# Super_Clokk_199774_2015_03_30.net
KiCad netlist of a schematic drawn in EAGLE
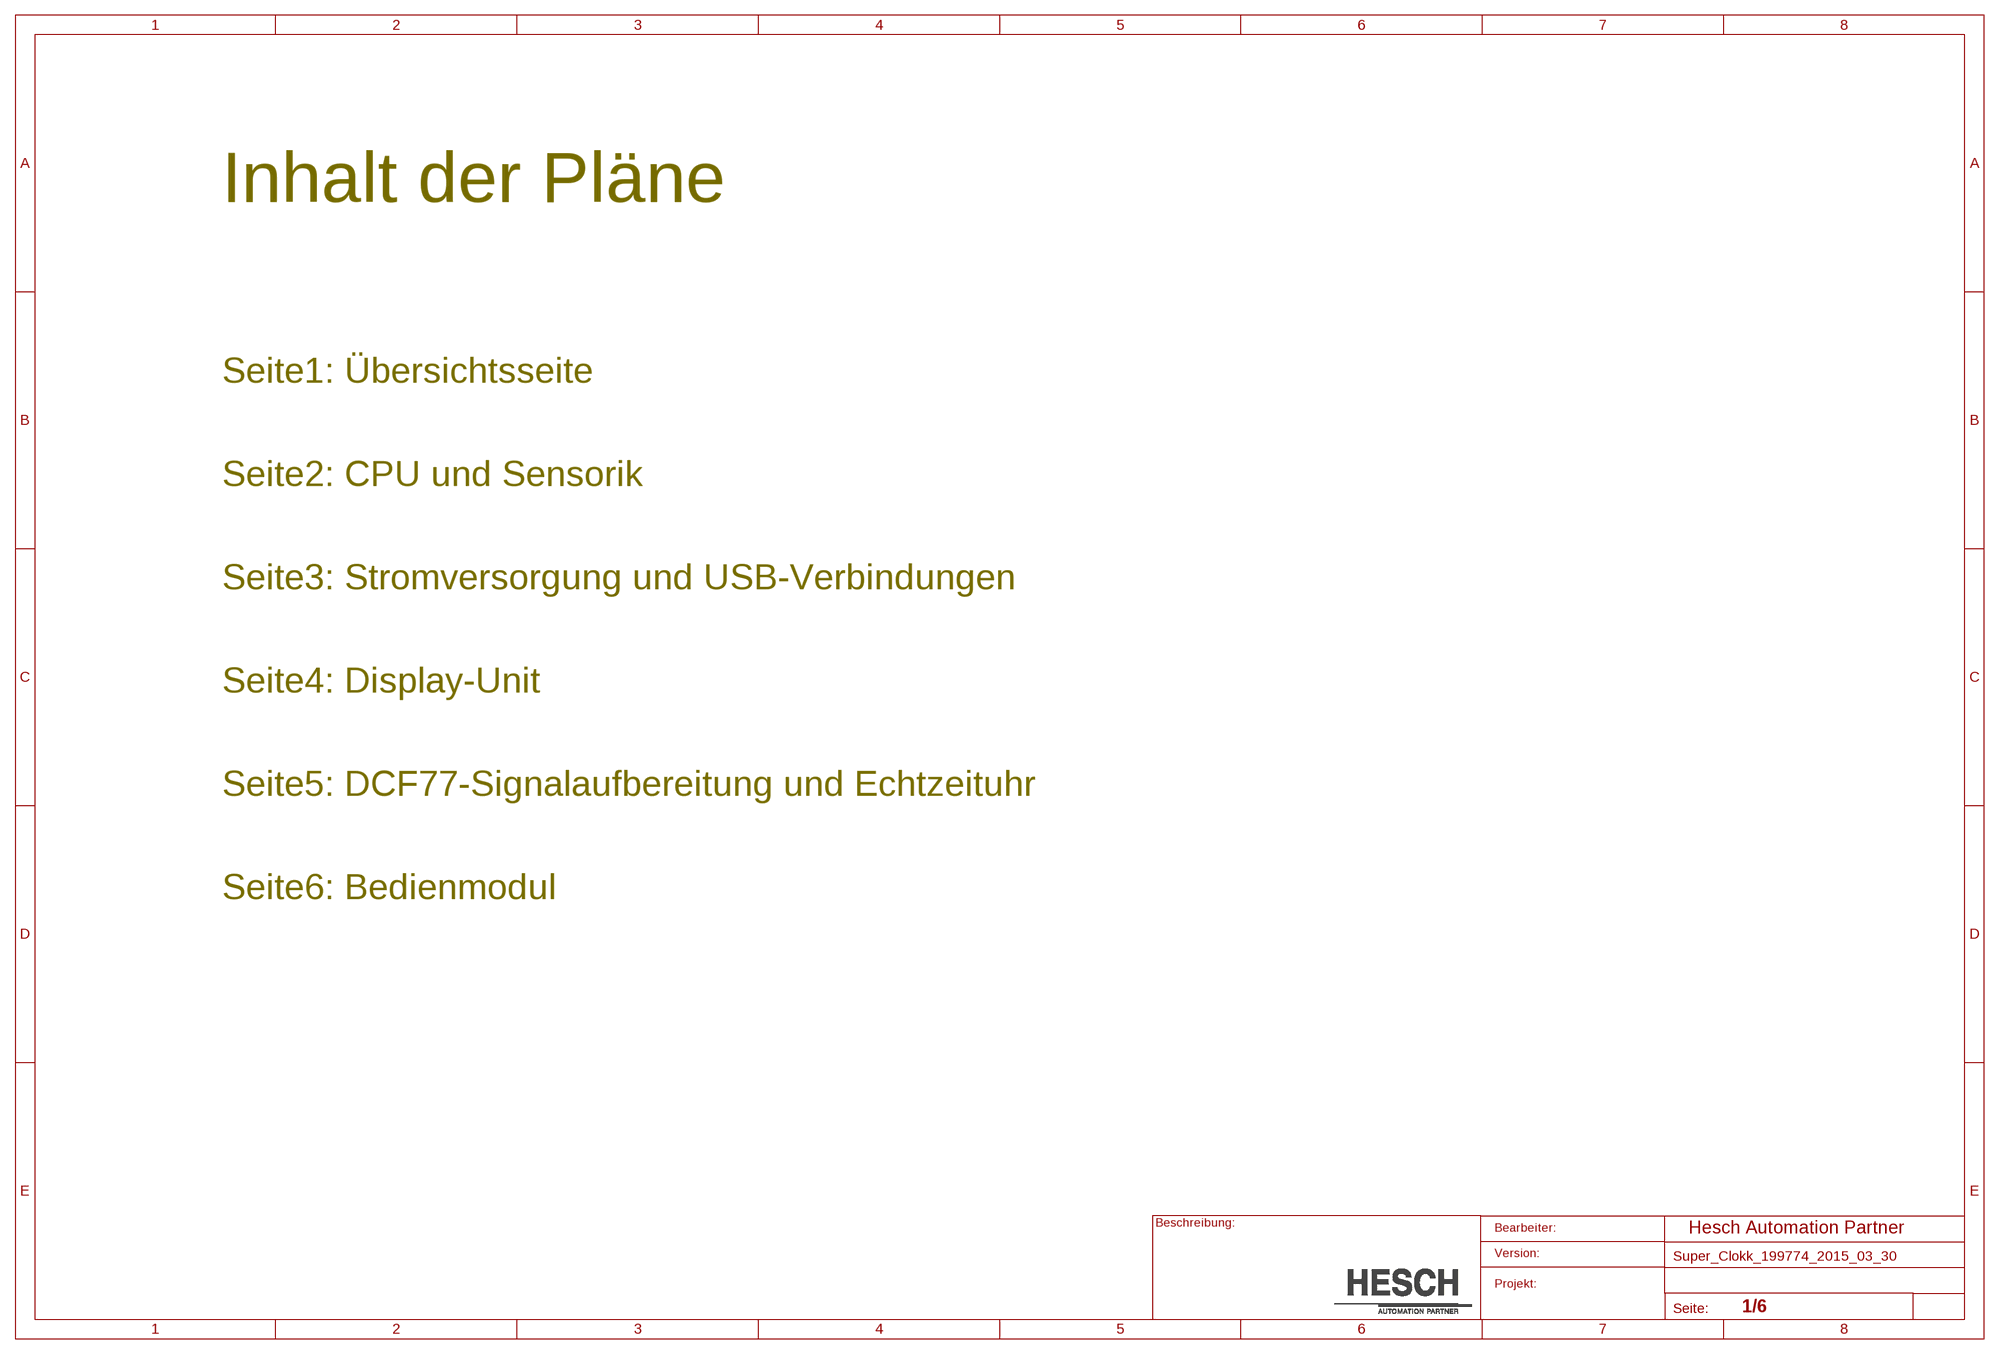
[diagram p0: schematic, sheet 1]
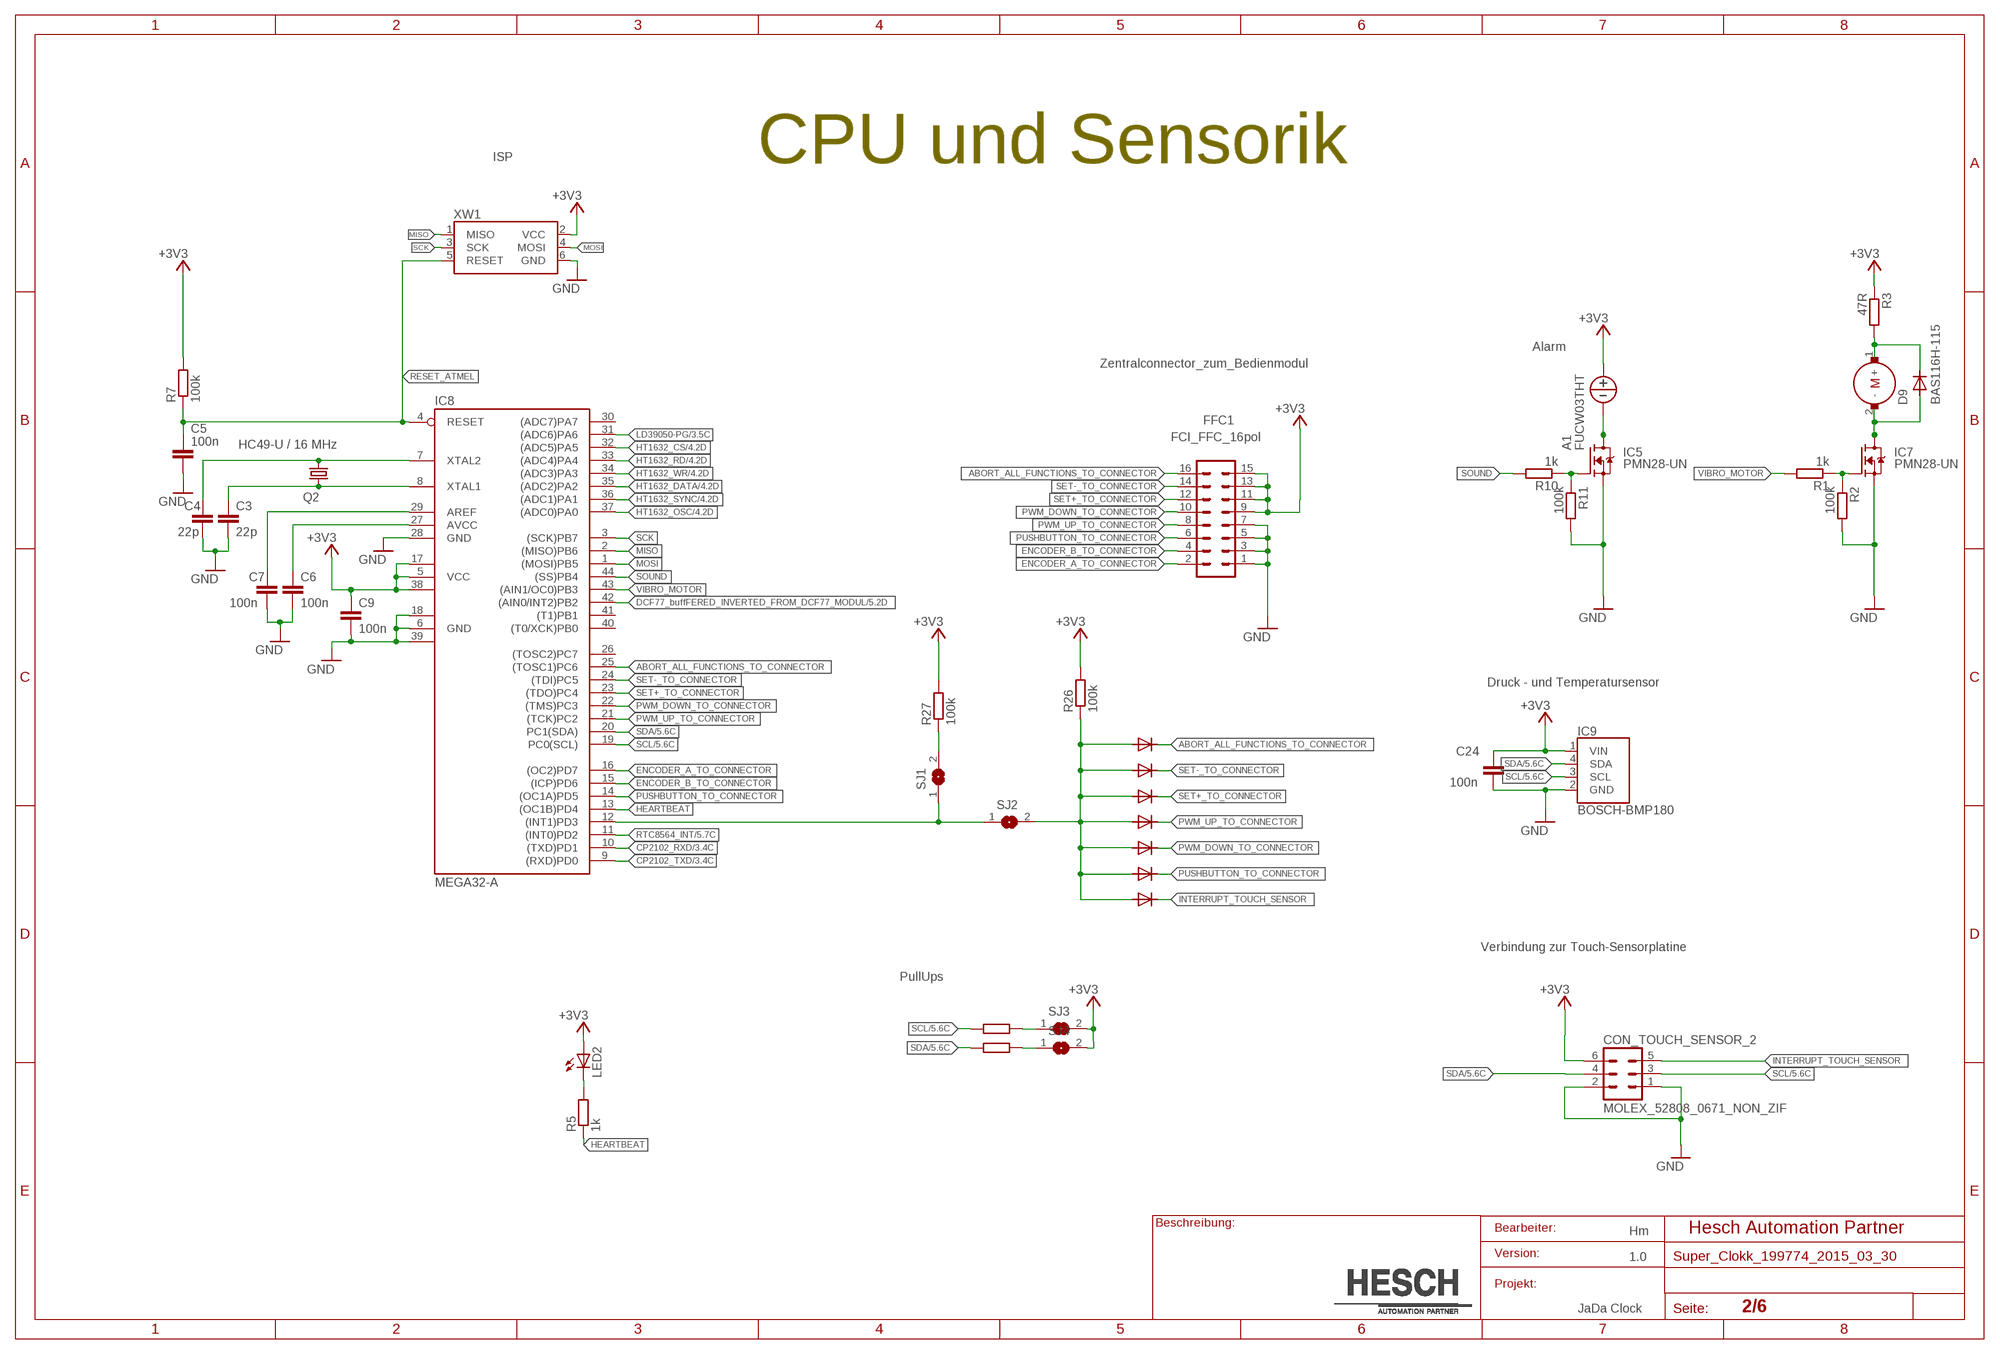
[diagram p1: schematic, sheet 2]
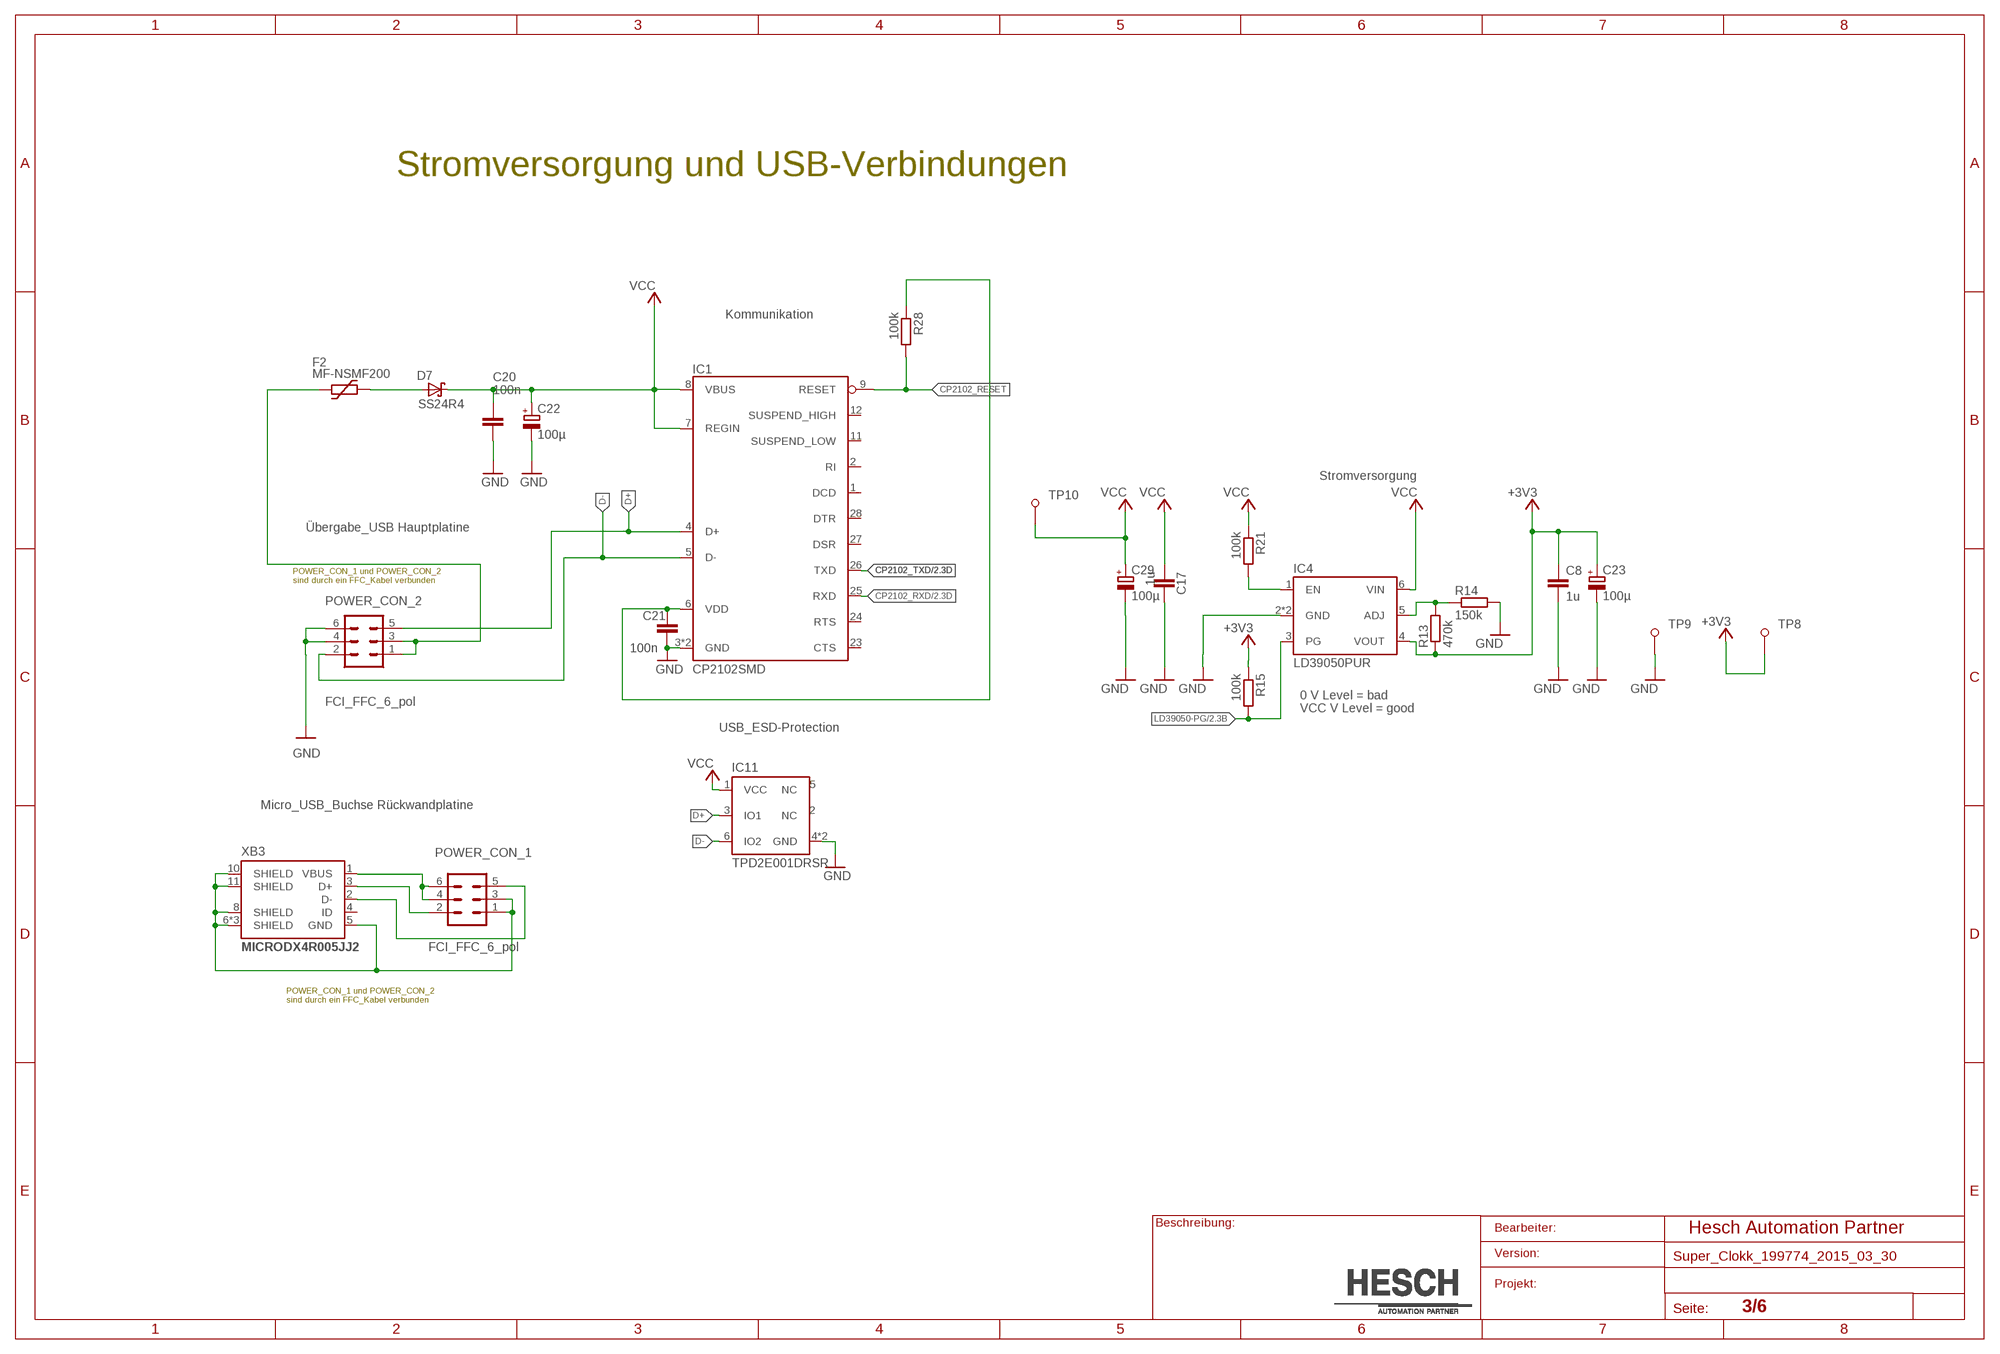
[diagram p2: schematic, sheet 3]
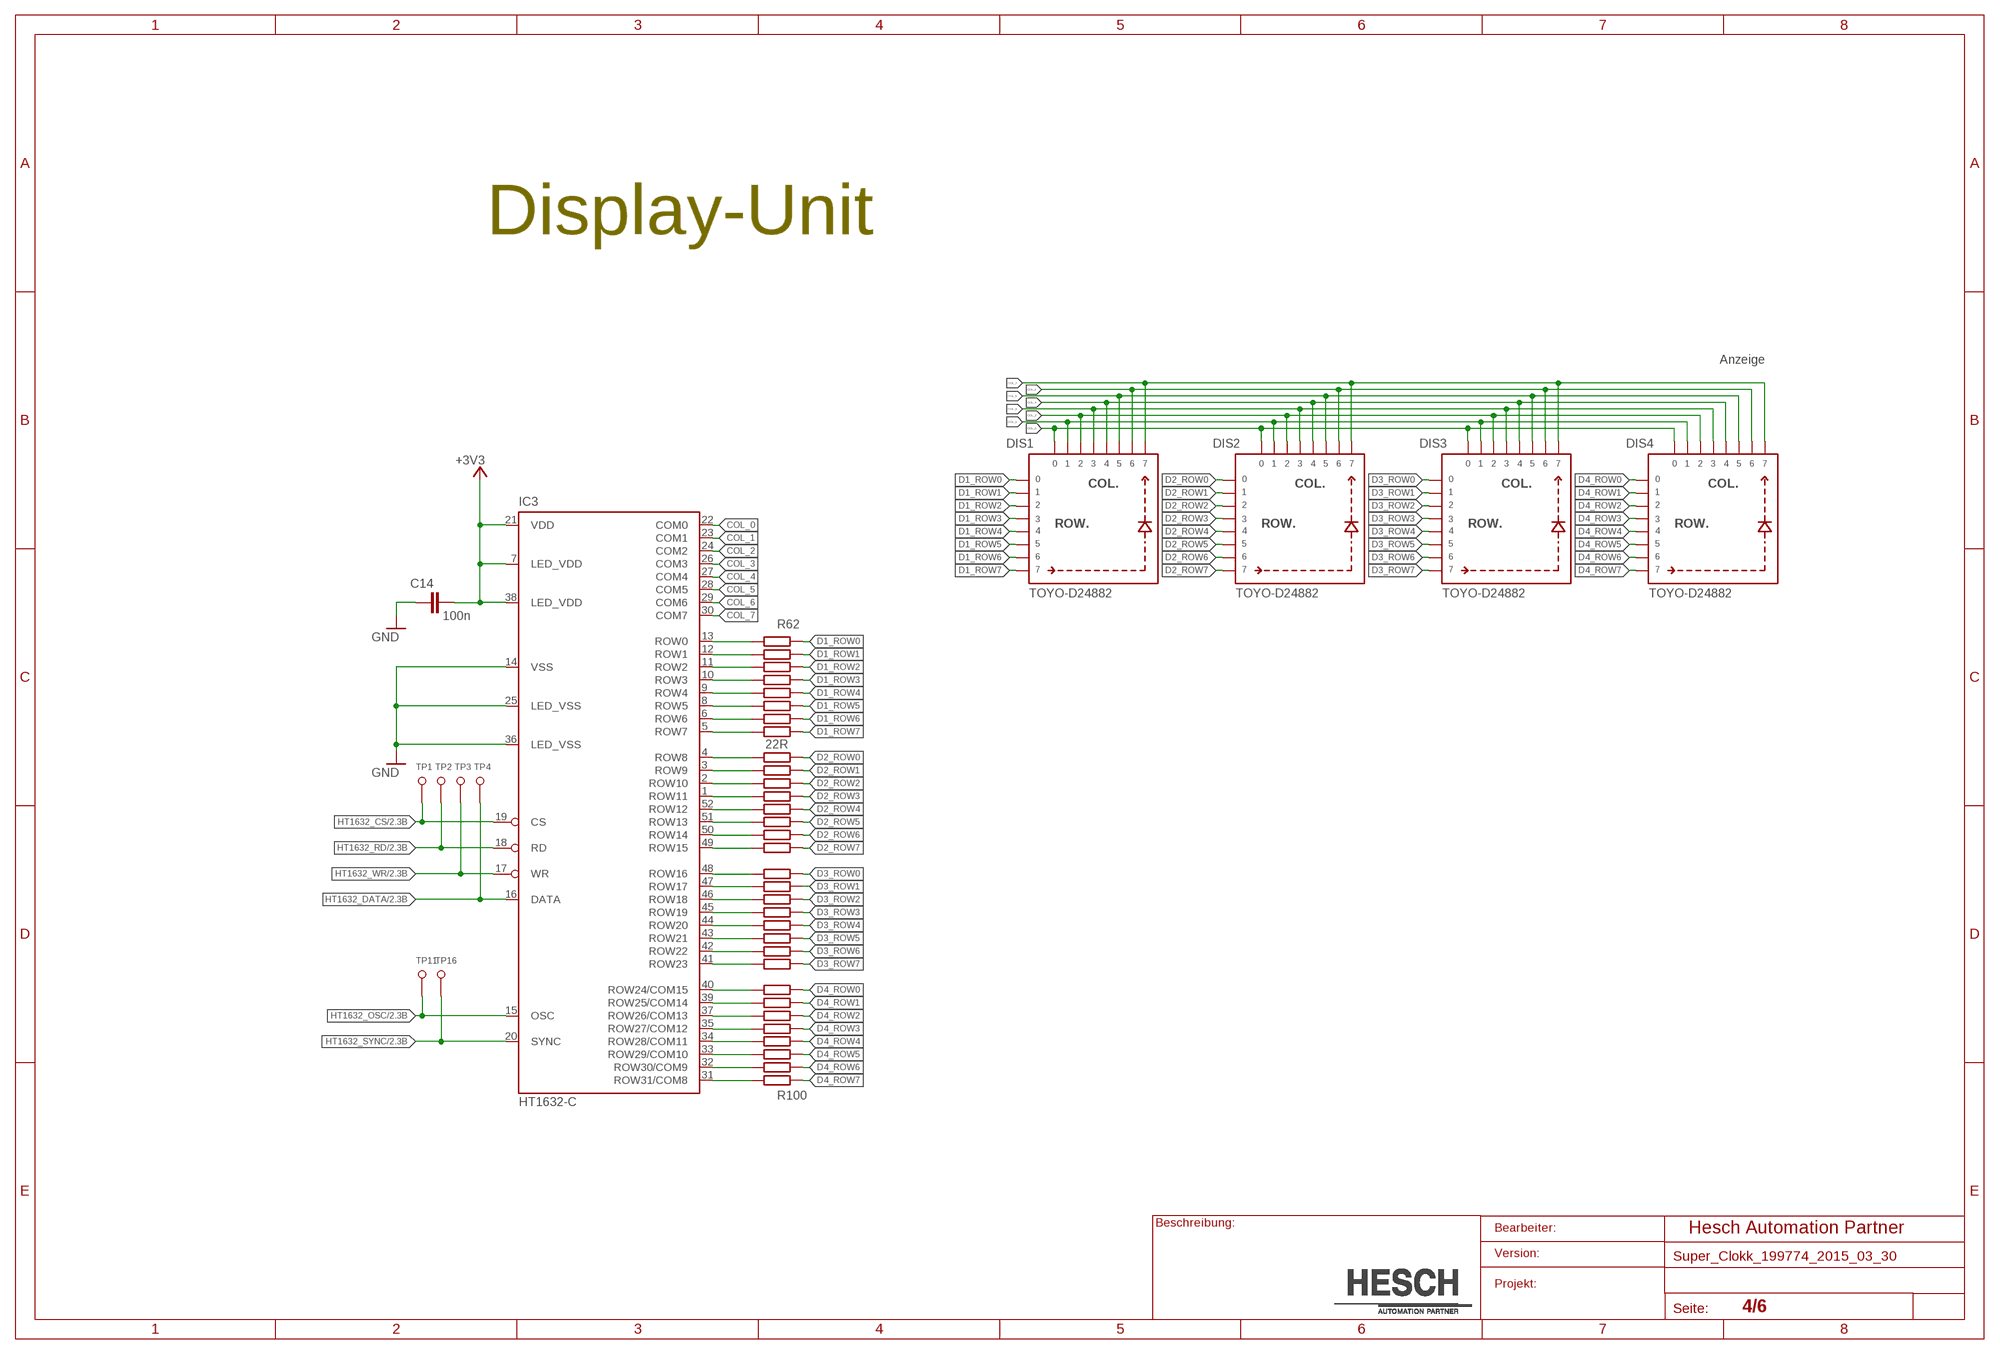
[diagram p3: schematic, sheet 4]
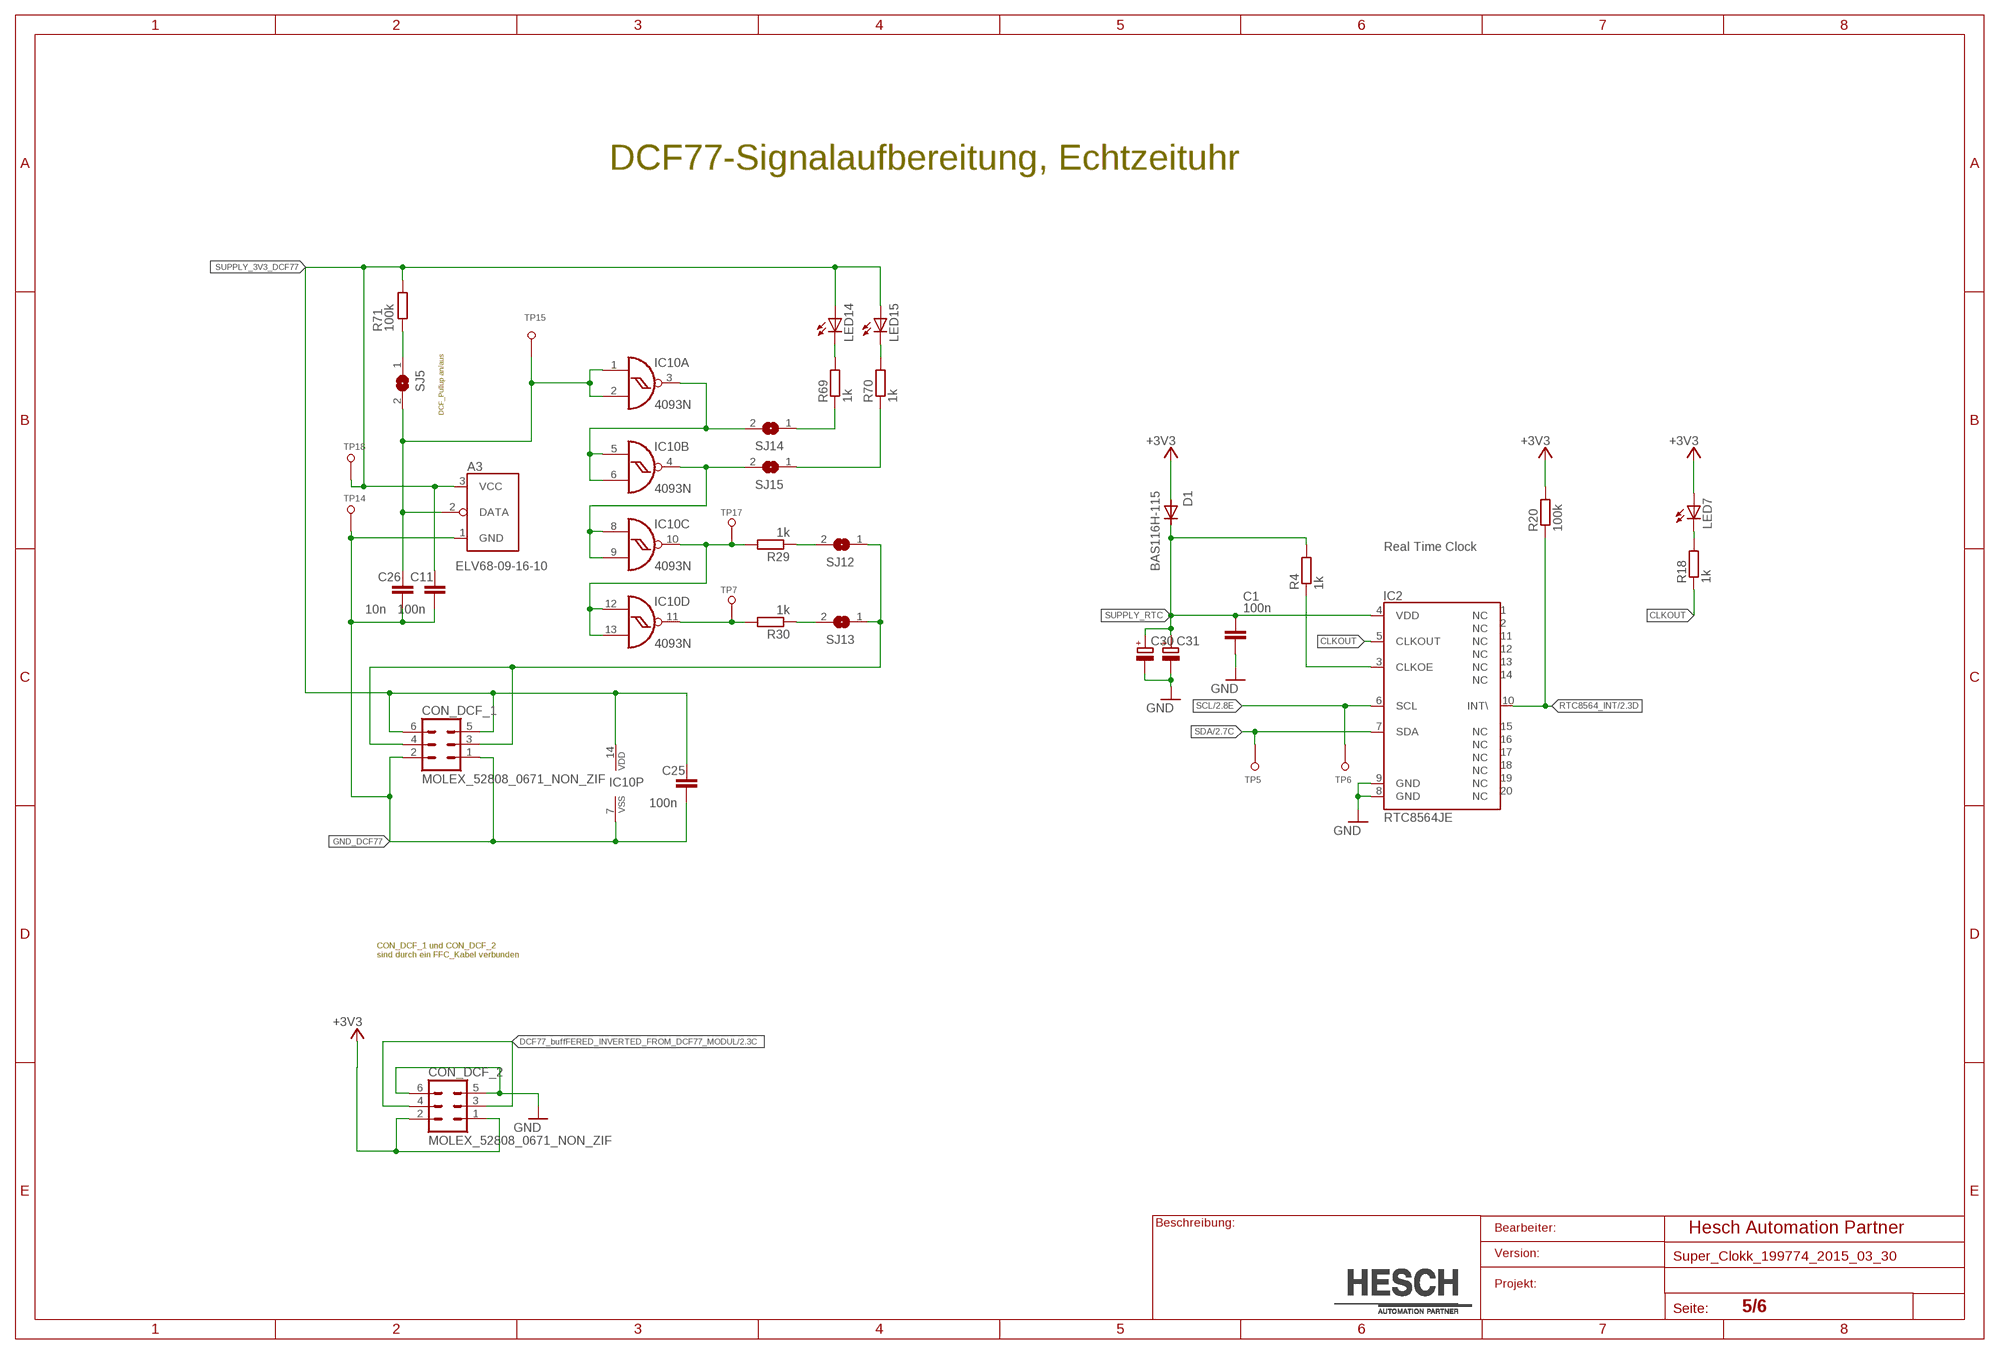
[diagram p4: schematic, sheet 5]
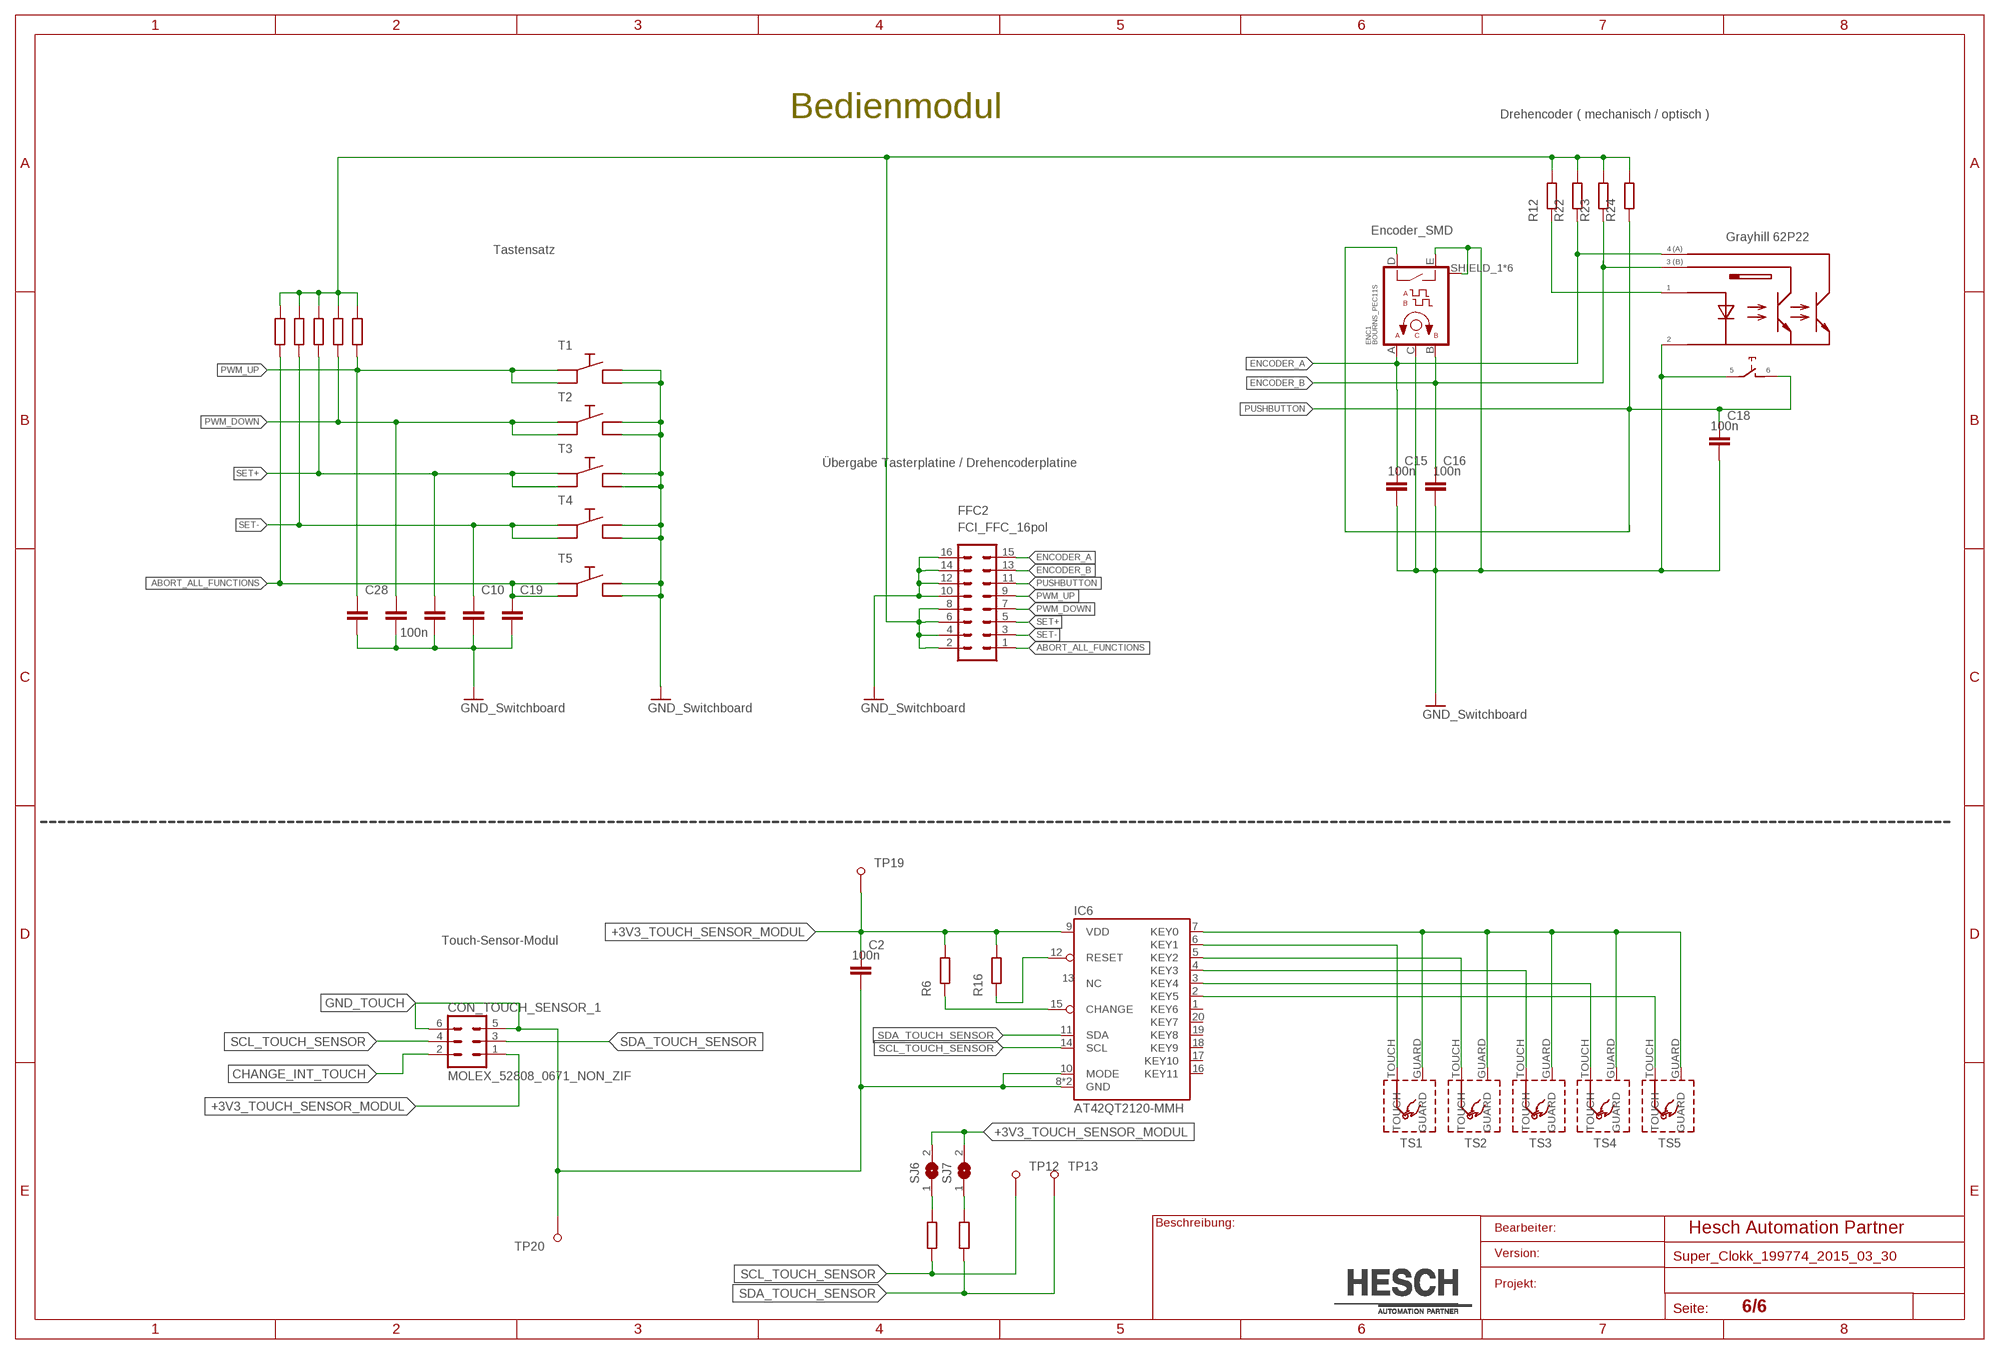
[diagram p5: schematic, sheet 6]

(export (version "E")
  (design (tool "Eeschema 10.0.6"))
  (components
    (comp (ref "C14")
      (value "100n")
      (footprint "eagle-import:C0805")
      (libsource (lib "eagle-import") (part "C-EUC0805"))
    )
    (comp (ref "DIS1")
      (value "TOYO-D24882")
      (footprint "eagle-import:TOYO")
      (libsource (lib "eagle-import") (part "TOYO-D24882"))
    )
    (comp (ref "DIS2")
      (value "TOYO-D24882")
      (footprint "eagle-import:TOYO")
      (libsource (lib "eagle-import") (part "TOYO-D24882"))
    )
    (comp (ref "DIS3")
      (value "TOYO-D24882")
      (footprint "eagle-import:TOYO")
      (libsource (lib "eagle-import") (part "TOYO-D24882"))
    )
    (comp (ref "DIS4")
      (value "TOYO-D24882")
      (footprint "eagle-import:TOYO")
      (libsource (lib "eagle-import") (part "TOYO-D24882"))
    )
    (comp (ref "IC3")
      (value "HT1632-C")
      (footprint "eagle-import:52PIN_OFP")
      (libsource (lib "eagle-import") (part "HT1632-C"))
    )
    (comp (ref "R62")
      (value "22R")
      (footprint "eagle-import:R0805")
      (libsource (lib "eagle-import") (part "R-EU_R0805"))
    )
    (comp (ref "R63")
      (value "22R")
      (footprint "eagle-import:R0805")
      (libsource (lib "eagle-import") (part "R-EU_R0805"))
    )
    (comp (ref "R65")
      (value "22R")
      (footprint "eagle-import:R0805")
      (libsource (lib "eagle-import") (part "R-EU_R0805"))
    )
    (comp (ref "R66")
      (value "22R")
      (footprint "eagle-import:R0805")
      (libsource (lib "eagle-import") (part "R-EU_R0805"))
    )
    (comp (ref "R67")
      (value "22R")
      (footprint "eagle-import:R0805")
      (libsource (lib "eagle-import") (part "R-EU_R0805"))
    )
    (comp (ref "R74")
      (value "22R")
      (footprint "eagle-import:R0805")
      (libsource (lib "eagle-import") (part "R-EU_R0805"))
    )
    (comp (ref "R75")
      (value "22R")
      (footprint "eagle-import:R0805")
      (libsource (lib "eagle-import") (part "R-EU_R0805"))
    )
    (comp (ref "R76")
      (value "22R")
      (footprint "eagle-import:R0805")
      (libsource (lib "eagle-import") (part "R-EU_R0805"))
    )
    (comp (ref "R77")
      (value "22R")
      (footprint "eagle-import:R0805")
      (libsource (lib "eagle-import") (part "R-EU_R0805"))
    )
    (comp (ref "R78")
      (value "22R")
      (footprint "eagle-import:R0805")
      (libsource (lib "eagle-import") (part "R-EU_R0805"))
    )
    (comp (ref "R79")
      (value "22R")
      (footprint "eagle-import:R0805")
      (libsource (lib "eagle-import") (part "R-EU_R0805"))
    )
    (comp (ref "R80")
      (value "22R")
      (footprint "eagle-import:R0805")
      (libsource (lib "eagle-import") (part "R-EU_R0805"))
    )
    (comp (ref "R81")
      (value "22R")
      (footprint "eagle-import:R0805")
      (libsource (lib "eagle-import") (part "R-EU_R0805"))
    )
    (comp (ref "R82")
      (value "22R")
      (footprint "eagle-import:R0805")
      (libsource (lib "eagle-import") (part "R-EU_R0805"))
    )
    (comp (ref "R83")
      (value "22R")
      (footprint "eagle-import:R0805")
      (libsource (lib "eagle-import") (part "R-EU_R0805"))
    )
    (comp (ref "R84")
      (value "22R")
      (footprint "eagle-import:R0805")
      (libsource (lib "eagle-import") (part "R-EU_R0805"))
    )
    (comp (ref "R85")
      (value "22R")
      (footprint "eagle-import:R0805")
      (libsource (lib "eagle-import") (part "R-EU_R0805"))
    )
    (comp (ref "R86")
      (value "22R")
      (footprint "eagle-import:R0805")
      (libsource (lib "eagle-import") (part "R-EU_R0805"))
    )
    (comp (ref "R87")
      (value "22R")
      (footprint "eagle-import:R0805")
      (libsource (lib "eagle-import") (part "R-EU_R0805"))
    )
    (comp (ref "R88")
      (value "22R")
      (footprint "eagle-import:R0805")
      (libsource (lib "eagle-import") (part "R-EU_R0805"))
    )
    (comp (ref "R89")
      (value "22R")
      (footprint "eagle-import:R0805")
      (libsource (lib "eagle-import") (part "R-EU_R0805"))
    )
    (comp (ref "R90")
      (value "22R")
      (footprint "eagle-import:R0805")
      (libsource (lib "eagle-import") (part "R-EU_R0805"))
    )
    (comp (ref "R91")
      (value "22R")
      (footprint "eagle-import:R0805")
      (libsource (lib "eagle-import") (part "R-EU_R0805"))
    )
    (comp (ref "R92")
      (value "22R")
      (footprint "eagle-import:R0805")
      (libsource (lib "eagle-import") (part "R-EU_R0805"))
    )
    (comp (ref "R93")
      (value "22R")
      (footprint "eagle-import:R0805")
      (libsource (lib "eagle-import") (part "R-EU_R0805"))
    )
    (comp (ref "R94")
      (value "22R")
      (footprint "eagle-import:R0805")
      (libsource (lib "eagle-import") (part "R-EU_R0805"))
    )
    (comp (ref "R95")
      (value "22R")
      (footprint "eagle-import:R0805")
      (libsource (lib "eagle-import") (part "R-EU_R0805"))
    )
    (comp (ref "R96")
      (value "22R")
      (footprint "eagle-import:R0805")
      (libsource (lib "eagle-import") (part "R-EU_R0805"))
    )
    (comp (ref "R97")
      (value "22R")
      (footprint "eagle-import:R0805")
      (libsource (lib "eagle-import") (part "R-EU_R0805"))
    )
    (comp (ref "R98")
      (value "22R")
      (footprint "eagle-import:R0805")
      (libsource (lib "eagle-import") (part "R-EU_R0805"))
    )
    (comp (ref "R99")
      (value "22R")
      (footprint "eagle-import:R0805")
      (libsource (lib "eagle-import") (part "R-EU_R0805"))
    )
    (comp (ref "R100")
      (value "22R")
      (footprint "eagle-import:R0805")
      (libsource (lib "eagle-import") (part "R-EU_R0805"))
    )
    (comp (ref "TP1")
      (value "PAD´S8")
      (footprint "eagle-import:THT-1X2,54")
      (libsource (lib "eagle-import") (part "PAD´S8"))
    )
    (comp (ref "TP2")
      (value "PAD´S8")
      (footprint "eagle-import:THT-1X2,54")
      (libsource (lib "eagle-import") (part "PAD´S8"))
    )
    (comp (ref "TP3")
      (value "PAD´S8")
      (footprint "eagle-import:THT-1X2,54")
      (libsource (lib "eagle-import") (part "PAD´S8"))
    )
    (comp (ref "TP4")
      (value "PAD´S8")
      (footprint "eagle-import:THT-1X2,54")
      (libsource (lib "eagle-import") (part "PAD´S8"))
    )
    (comp (ref "TP11")
      (value "PAD´S8")
      (footprint "eagle-import:THT-1X2,54")
      (libsource (lib "eagle-import") (part "PAD´S8"))
    )
    (comp (ref "TP16")
      (value "PAD´S8")
      (footprint "eagle-import:THT-1X2,54")
      (libsource (lib "eagle-import") (part "PAD´S8"))
    )
    (comp (ref "C8")
      (value "1u")
      (footprint "eagle-import:C0805K")
      (libsource (lib "eagle-import") (part "resistor_C-EUC0805K"))
    )
    (comp (ref "C17")
      (value "1u")
      (footprint "eagle-import:C0805K")
      (libsource (lib "eagle-import") (part "resistor_C-EUC0805K"))
    )
    (comp (ref "C20")
      (value "100n")
      (footprint "eagle-import:C0805")
      (libsource (lib "eagle-import") (part "C-EUC0805"))
    )
    (comp (ref "C21")
      (value "100n")
      (footprint "eagle-import:C0805")
      (libsource (lib "eagle-import") (part "C-EUC0805"))
    )
    (comp (ref "C22")
      (value "100µ")
      (footprint "eagle-import:SMC_D")
      (libsource (lib "eagle-import") (part "CPOL-EUSMCD"))
    )
    (comp (ref "C23")
      (value "100µ")
      (footprint "eagle-import:SMC_D")
      (libsource (lib "eagle-import") (part "CPOL-EUSMCD"))
    )
    (comp (ref "C29")
      (value "100µ")
      (footprint "eagle-import:SMC_D")
      (libsource (lib "eagle-import") (part "CPOL-EUSMCD"))
    )
    (comp (ref "D7")
      (value "SS24R4")
      (footprint "eagle-import:DO-214AA_SMB")
      (libsource (lib "eagle-import") (part "SS24R4"))
    )
    (comp (ref "F2")
      (value "MF-NSMF200")
      (footprint "eagle-import:1206L")
      (libsource (lib "eagle-import") (part "1206L-MF-NSMF050-2"))
    )
    (comp (ref "IC1")
      (value "CP2102SMD")
      (footprint "eagle-import:QFN28")
      (libsource (lib "eagle-import") (part "CP2102SMD"))
    )
    (comp (ref "IC4")
      (value "LD39050PUR")
      (footprint "eagle-import:DFN6")
      (libsource (lib "eagle-import") (part "LD39050PUR"))
    )
    (comp (ref "IC11")
      (value "TPD2E001DRSR")
      (footprint "eagle-import:DRS")
      (libsource (lib "eagle-import") (part "TPD2E001DRSR"))
    )
    (comp (ref "POWER_CON_1")
      (value "FCI_FFC_6_pol")
      (footprint "eagle-import:MOLEX_52808-0671_NON_ZIF")
      (libsource (lib "eagle-import") (part "MOLEX_52808_0671_NON_ZIF"))
    )
    (comp (ref "POWER_CON_2")
      (value "FCI_FFC_6_pol")
      (footprint "eagle-import:MOLEX_52808-0671_NON_ZIF")
      (libsource (lib "eagle-import") (part "MOLEX_52808_0671_NON_ZIF"))
    )
    (comp (ref "R13")
      (value "470k")
      (footprint "eagle-import:R0603")
      (libsource (lib "eagle-import") (part "resistor_R-EU_R0603"))
    )
    (comp (ref "R14")
      (value "150k")
      (footprint "eagle-import:R0603")
      (libsource (lib "eagle-import") (part "resistor_R-EU_R0603"))
    )
    (comp (ref "R15")
      (value "100k")
      (footprint "eagle-import:R0805")
      (libsource (lib "eagle-import") (part "R-EU_R0805"))
    )
    (comp (ref "R21")
      (value "100k")
      (footprint "eagle-import:R0805")
      (libsource (lib "eagle-import") (part "R-EU_R0805"))
    )
    (comp (ref "R28")
      (value "100k")
      (footprint "eagle-import:R0805")
      (libsource (lib "eagle-import") (part "R-EU_R0805"))
    )
    (comp (ref "TP8")
      (value "PAD´S8")
      (footprint "eagle-import:THT-1X2,54")
      (libsource (lib "eagle-import") (part "PAD´S8"))
    )
    (comp (ref "TP9")
      (value "PAD´S8")
      (footprint "eagle-import:THT-1X2,54")
      (libsource (lib "eagle-import") (part "PAD´S8"))
    )
    (comp (ref "TP10")
      (value "PAD´S8")
      (footprint "eagle-import:THT-1X2,54")
      (libsource (lib "eagle-import") (part "PAD´S8"))
    )
    (comp (ref "XB3")
      (value "MICRODX4R005JJ2")
      (footprint "eagle-import:MICRO_NEU")
      (libsource (lib "eagle-import") (part "MICRODX4R005JJ2"))
    )
    (comp (ref "C2")
      (value "100n")
      (footprint "eagle-import:C0805")
      (libsource (lib "eagle-import") (part "C-EUC0805"))
    )
    (comp (ref "C10")
      (value "100n")
      (footprint "eagle-import:C0805")
      (libsource (lib "eagle-import") (part "C-EUC0805"))
    )
    (comp (ref "C12")
      (value "100n")
      (footprint "eagle-import:C0805")
      (libsource (lib "eagle-import") (part "C-EUC0805"))
    )
    (comp (ref "C15")
      (value "100n")
      (footprint "eagle-import:C0805")
      (libsource (lib "eagle-import") (part "C-EUC0805"))
    )
    (comp (ref "C16")
      (value "100n")
      (footprint "eagle-import:C0805")
      (libsource (lib "eagle-import") (part "C-EUC0805"))
    )
    (comp (ref "C18")
      (value "100n")
      (footprint "eagle-import:C0805")
      (libsource (lib "eagle-import") (part "C-EUC0805"))
    )
    (comp (ref "C19")
      (value "100n")
      (footprint "eagle-import:C0805")
      (libsource (lib "eagle-import") (part "C-EUC0805"))
    )
    (comp (ref "C27")
      (value "100n")
      (footprint "eagle-import:C0805")
      (libsource (lib "eagle-import") (part "C-EUC0805"))
    )
    (comp (ref "C28")
      (value "100n")
      (footprint "eagle-import:C0805")
      (libsource (lib "eagle-import") (part "C-EUC0805"))
    )
    (comp (ref "CON_TOUCH_SENSOR_1")
      (value "MOLEX_52808_0671_NON_ZIF")
      (footprint "eagle-import:MOLEX_52808-0671_NON_ZIF")
      (libsource (lib "eagle-import") (part "MOLEX_52808_0671_NON_ZIF"))
    )
    (comp (ref "ENC1")
      (value "BOURNS_PEC11S")
      (footprint "eagle-import:BOURNS_PEC11S")
      (libsource (lib "eagle-import") (part "BOURNS_PEC11S"))
    )
    (comp (ref "ENC2")
      (value "Grayhill 62P22")
      (footprint "eagle-import:62P22")
      (libsource (lib "eagle-import") (part "62P22"))
    )
    (comp (ref "FFC2")
      (value "FCI_FFC_16pol")
      (footprint "eagle-import:MOLEX_52808_1671_NON_ZIF")
      (libsource (lib "eagle-import") (part "MOLEX_52808-1671_NON_ZIF"))
    )
    (comp (ref "IC6")
      (value "AT42QT2120-MMH")
      (footprint "eagle-import:VQFN-20")
      (libsource (lib "eagle-import") (part "AT42QT2120-MMH"))
    )
    (comp (ref "R6")
      (value "10k")
      (footprint "eagle-import:R0805")
      (libsource (lib "eagle-import") (part "R-EU_R0805"))
    )
    (comp (ref "R8")
      (value "100k")
      (footprint "eagle-import:R0805")
      (libsource (lib "eagle-import") (part "R-EU_R0805"))
    )
    (comp (ref "R9")
      (value "100k")
      (footprint "eagle-import:R0805")
      (libsource (lib "eagle-import") (part "R-EU_R0805"))
    )
    (comp (ref "R12")
      (value "100R")
      (footprint "eagle-import:R0805")
      (libsource (lib "eagle-import") (part "R-EU_R0805"))
    )
    (comp (ref "R16")
      (value "10k")
      (footprint "eagle-import:R0805")
      (libsource (lib "eagle-import") (part "R-EU_R0805"))
    )
    (comp (ref "R17")
      (value "10k")
      (footprint "eagle-import:R0805")
      (libsource (lib "eagle-import") (part "R-EU_R0805"))
    )
    (comp (ref "R19")
      (value "10k")
      (footprint "eagle-import:R0805")
      (libsource (lib "eagle-import") (part "R-EU_R0805"))
    )
    (comp (ref "R22")
      (value "10k")
      (footprint "eagle-import:R0805")
      (libsource (lib "eagle-import") (part "R-EU_R0805"))
    )
    (comp (ref "R23")
      (value "10k")
      (footprint "eagle-import:R0805")
      (libsource (lib "eagle-import") (part "R-EU_R0805"))
    )
    (comp (ref "R24")
      (value "10k")
      (footprint "eagle-import:R0805")
      (libsource (lib "eagle-import") (part "R-EU_R0805"))
    )
    (comp (ref "R25")
      (value "100k")
      (footprint "eagle-import:R0805")
      (libsource (lib "eagle-import") (part "R-EU_R0805"))
    )
    (comp (ref "R64")
      (value "100k")
      (footprint "eagle-import:R0805")
      (libsource (lib "eagle-import") (part "R-EU_R0805"))
    )
    (comp (ref "R72")
      (value "100k")
      (footprint "eagle-import:R0805")
      (libsource (lib "eagle-import") (part "R-EU_R0805"))
    )
    (comp (ref "SJ6") (value "SJ") (footprint "eagle-import:SJ") (libsource (lib "eagle-import") (part "SJ")))
    (comp (ref "SJ7") (value "SJ") (footprint "eagle-import:SJ") (libsource (lib "eagle-import") (part "SJ")))
    (comp (ref "T1")
      (value "OMRON-B3S-1002P")
      (footprint "eagle-import:B3S-1002P")
      (libsource (lib "eagle-import") (part "OMRON-B3S-1002P"))
    )
    (comp (ref "T2")
      (value "OMRON-B3S-1002P")
      (footprint "eagle-import:B3S-1002P")
      (libsource (lib "eagle-import") (part "OMRON-B3S-1002P"))
    )
    (comp (ref "T3")
      (value "OMRON-B3S-1002P")
      (footprint "eagle-import:B3S-1002P")
      (libsource (lib "eagle-import") (part "OMRON-B3S-1002P"))
    )
    (comp (ref "T4")
      (value "OMRON-B3S-1002P")
      (footprint "eagle-import:B3S-1002P")
      (libsource (lib "eagle-import") (part "OMRON-B3S-1002P"))
    )
    (comp (ref "T5")
      (value "OMRON-B3S-1002P")
      (footprint "eagle-import:B3S-1002P")
      (libsource (lib "eagle-import") (part "OMRON-B3S-1002P"))
    )
    (comp (ref "TP12")
      (value "PAD´S8")
      (footprint "eagle-import:THT-1X2,54")
      (libsource (lib "eagle-import") (part "PAD´S8"))
    )
    (comp (ref "TP13")
      (value "PAD´S8")
      (footprint "eagle-import:THT-1X2,54")
      (libsource (lib "eagle-import") (part "PAD´S8"))
    )
    (comp (ref "TP19")
      (value "PAD´S8")
      (footprint "eagle-import:THT-1X2,54")
      (libsource (lib "eagle-import") (part "PAD´S8"))
    )
    (comp (ref "TP20")
      (value "PAD´S8")
      (footprint "eagle-import:THT-1X2,54")
      (libsource (lib "eagle-import") (part "PAD´S8"))
    )
    (comp (ref "TS1")
      (value "TOUCH_SENSOR_14MM")
      (footprint "eagle-import:TOUCH_SENSOR_14MM")
      (libsource (lib "eagle-import") (part "TOUCH_SENSOR_14MM"))
    )
    (comp (ref "TS2")
      (value "TOUCH_SENSOR_14MM")
      (footprint "eagle-import:TOUCH_SENSOR_14MM")
      (libsource (lib "eagle-import") (part "TOUCH_SENSOR_14MM"))
    )
    (comp (ref "TS3")
      (value "TOUCH_SENSOR_14MM")
      (footprint "eagle-import:TOUCH_SENSOR_14MM")
      (libsource (lib "eagle-import") (part "TOUCH_SENSOR_14MM"))
    )
    (comp (ref "TS4")
      (value "TOUCH_SENSOR_14MM")
      (footprint "eagle-import:TOUCH_SENSOR_14MM")
      (libsource (lib "eagle-import") (part "TOUCH_SENSOR_14MM"))
    )
    (comp (ref "TS5")
      (value "TOUCH_SENSOR_14MM")
      (footprint "eagle-import:TOUCH_SENSOR_14MM")
      (libsource (lib "eagle-import") (part "TOUCH_SENSOR_14MM"))
    )
    (comp (ref "A1")
      (value "FUCW03THT")
      (footprint "eagle-import:FUCW03")
      (libsource (lib "eagle-import") (part "FUCW03THT"))
    )
    (comp (ref "C3")
      (value "22p")
      (footprint "eagle-import:C0805K")
      (libsource (lib "eagle-import") (part "resistor_C-EUC0805K"))
    )
    (comp (ref "C4")
      (value "22p")
      (footprint "eagle-import:C0805K")
      (libsource (lib "eagle-import") (part "resistor_C-EUC0805K"))
    )
    (comp (ref "C5")
      (value "100n")
      (footprint "eagle-import:C0805")
      (libsource (lib "eagle-import") (part "C-EUC0805"))
    )
    (comp (ref "C6")
      (value "100n")
      (footprint "eagle-import:C0805")
      (libsource (lib "eagle-import") (part "C-EUC0805"))
    )
    (comp (ref "C7")
      (value "100n")
      (footprint "eagle-import:C0805")
      (libsource (lib "eagle-import") (part "C-EUC0805"))
    )
    (comp (ref "C9")
      (value "100n")
      (footprint "eagle-import:C0805")
      (libsource (lib "eagle-import") (part "C-EUC0805"))
    )
    (comp (ref "C24")
      (value "100n")
      (footprint "eagle-import:C0805")
      (libsource (lib "eagle-import") (part "C-EUC0805"))
    )
    (comp (ref "CON_TOUCH_SENSOR_2")
      (value "MOLEX_52808_0671_NON_ZIF")
      (footprint "eagle-import:MOLEX_52808-0671_NON_ZIF")
      (libsource (lib "eagle-import") (part "MOLEX_52808_0671_NON_ZIF"))
    )
    (comp (ref "D2")
      (value "BAS116H-115")
      (footprint "eagle-import:SOD123")
      (libsource (lib "eagle-import") (part "BAS116H-115"))
    )
    (comp (ref "D3")
      (value "BAS116H-115")
      (footprint "eagle-import:SOD123")
      (libsource (lib "eagle-import") (part "BAS116H-115"))
    )
    (comp (ref "D4")
      (value "BAS116H-115")
      (footprint "eagle-import:SOD123")
      (libsource (lib "eagle-import") (part "BAS116H-115"))
    )
    (comp (ref "D5")
      (value "BAS116H-115")
      (footprint "eagle-import:SOD123")
      (libsource (lib "eagle-import") (part "BAS116H-115"))
    )
    (comp (ref "D6")
      (value "BAS116H-115")
      (footprint "eagle-import:SOD123")
      (libsource (lib "eagle-import") (part "BAS116H-115"))
    )
    (comp (ref "D8")
      (value "BAS116H-115")
      (footprint "eagle-import:SOD123")
      (libsource (lib "eagle-import") (part "BAS116H-115"))
    )
    (comp (ref "D9")
      (value "BAS116H-115")
      (footprint "eagle-import:SOD123")
      (libsource (lib "eagle-import") (part "BAS116H-115"))
    )
    (comp (ref "D10")
      (value "BAS116H-115")
      (footprint "eagle-import:SOD123")
      (libsource (lib "eagle-import") (part "BAS116H-115"))
    )
    (comp (ref "FFC1")
      (value "FCI_FFC_16pol")
      (footprint "eagle-import:MOLEX_52808_1671_NON_ZIF")
      (libsource (lib "eagle-import") (part "MOLEX_52808-1671_NON_ZIF"))
    )
    (comp (ref "IC5")
      (value "PMN28-UN")
      (footprint "eagle-import:SOT457")
      (libsource (lib "eagle-import") (part "PMN28-UN"))
    )
    (comp (ref "IC7")
      (value "PMN28-UN")
      (footprint "eagle-import:SOT457")
      (libsource (lib "eagle-import") (part "PMN28-UN"))
    )
    (comp (ref "IC8")
      (value "MEGA32-A")
      (footprint "eagle-import:TQFP44")
      (fields (field (name "MPN") "ATMEGA32-16AU"))
      (libsource (lib "eagle-import") (part "MEGA32-A"))
    )
    (comp (ref "IC9")
      (value "BOSCH-BMP180")
      (footprint "eagle-import:10X13MM")
      (libsource (lib "eagle-import") (part "BOSCH-BMP180"))
    )
    (comp (ref "LED2")
      (value "LEDCHIPLED_0805")
      (footprint "eagle-import:CHIPLED_0805")
      (libsource (lib "eagle-import") (part "LEDCHIPLED_0805"))
    )
    (comp (ref "M1")
      (value "VIBROMOTORTHT432A")
      (footprint "eagle-import:LA4-432A")
      (libsource (lib "eagle-import") (part "VIBROMOTORTHT432A"))
    )
    (comp (ref "Q2")
      (value "HC49-U / 16 MHz")
      (footprint "eagle-import:HC49")
      (libsource (lib "eagle-import") (part "HC49-U"))
    )
    (comp (ref "R1")
      (value "1k")
      (footprint "eagle-import:R0805")
      (libsource (lib "eagle-import") (part "R-EU_R0805"))
    )
    (comp (ref "R2")
      (value "100k")
      (footprint "eagle-import:R0805")
      (libsource (lib "eagle-import") (part "R-EU_R0805"))
    )
    (comp (ref "R3")
      (value "47R")
      (footprint "eagle-import:R0805")
      (libsource (lib "eagle-import") (part "R-EU_R0805"))
    )
    (comp (ref "R5")
      (value "1k")
      (footprint "eagle-import:R0805")
      (libsource (lib "eagle-import") (part "R-EU_R0805"))
    )
    (comp (ref "R7")
      (value "100k")
      (footprint "eagle-import:R0805")
      (libsource (lib "eagle-import") (part "R-EU_R0805"))
    )
    (comp (ref "R10")
      (value "1k")
      (footprint "eagle-import:R0805")
      (libsource (lib "eagle-import") (part "R-EU_R0805"))
    )
    (comp (ref "R11")
      (value "100k")
      (footprint "eagle-import:R0805")
      (libsource (lib "eagle-import") (part "R-EU_R0805"))
    )
    (comp (ref "R26")
      (value "100k")
      (footprint "eagle-import:R0805")
      (libsource (lib "eagle-import") (part "R-EU_R0805"))
    )
    (comp (ref "R27")
      (value "100k")
      (footprint "eagle-import:R0805")
      (libsource (lib "eagle-import") (part "R-EU_R0805"))
    )
    (comp (ref "R52")
      (value "4,7k")
      (footprint "eagle-import:R0805")
      (libsource (lib "eagle-import") (part "R-EU_R0805"))
    )
    (comp (ref "R53")
      (value "4,7k")
      (footprint "eagle-import:R0805")
      (libsource (lib "eagle-import") (part "R-EU_R0805"))
    )
    (comp (ref "SJ1") (value "SJ") (footprint "eagle-import:SJ") (libsource (lib "eagle-import") (part "SJ")))
    (comp (ref "SJ2") (value "SJ") (footprint "eagle-import:SJ") (libsource (lib "eagle-import") (part "SJ")))
    (comp (ref "SJ3") (value "SJ") (footprint "eagle-import:SJ") (libsource (lib "eagle-import") (part "SJ")))
    (comp (ref "SJ4") (value "SJ") (footprint "eagle-import:SJ") (libsource (lib "eagle-import") (part "SJ")))
    (comp (ref "XW1")
      (value "WSL6")
      (footprint "eagle-import:WSL")
      (libsource (lib "eagle-import") (part "WSL6"))
    )
    (comp (ref "A3")
      (value "ELV68-09-16-10")
      (footprint "eagle-import:18X23MM")
      (libsource (lib "eagle-import") (part "ELV68-09-16-10"))
    )
    (comp (ref "C1")
      (value "100n")
      (footprint "eagle-import:C0805")
      (libsource (lib "eagle-import") (part "C-EUC0805"))
    )
    (comp (ref "C11")
      (value "100n")
      (footprint "eagle-import:C0805")
      (libsource (lib "eagle-import") (part "C-EUC0805"))
    )
    (comp (ref "C25")
      (value "100n")
      (footprint "eagle-import:C0805")
      (libsource (lib "eagle-import") (part "C-EUC0805"))
    )
    (comp (ref "C26")
      (value "10n")
      (footprint "eagle-import:C0805")
      (libsource (lib "eagle-import") (part "C-EUC0805"))
    )
    (comp (ref "C30")
      (value "PANASONIC-EN&SD-SERIESTHT_1")
      (footprint "eagle-import:PANASONIC_SD_SERIES_STEHEND")
      (libsource (lib "eagle-import") (part "PANASONIC-EN&SD-SERIESTHT_1"))
    )
    (comp (ref "C31")
      (value "PANASONIC-EN&SD-SERIESTHT")
      (footprint "eagle-import:PANASONIC_SD_SERIES_LIEGEND")
      (libsource (lib "eagle-import") (part "PANASONIC-EN&SD-SERIESTHT"))
    )
    (comp (ref "CON_DCF_1")
      (value "MOLEX_52808_0671_NON_ZIF")
      (footprint "eagle-import:MOLEX_52808-0671_NON_ZIF")
      (libsource (lib "eagle-import") (part "MOLEX_52808_0671_NON_ZIF"))
    )
    (comp (ref "CON_DCF_2")
      (value "MOLEX_52808_0671_NON_ZIF")
      (footprint "eagle-import:MOLEX_52808-0671_NON_ZIF")
      (libsource (lib "eagle-import") (part "MOLEX_52808_0671_NON_ZIF"))
    )
    (comp (ref "D1")
      (value "BAS116H-115")
      (footprint "eagle-import:SOD123")
      (libsource (lib "eagle-import") (part "BAS116H-115"))
    )
    (comp (ref "IC2")
      (value "RTC8564JESMD")
      (footprint "eagle-import:VSOJ20")
      (libsource (lib "eagle-import") (part "RTC8564JESMD"))
    )
    (comp (ref "IC10")
      (value "4093N")
      (footprint "eagle-import:DIL14")
      (libsource (lib "eagle-import") (part "4093N"))
    )
    (comp (ref "LED7")
      (value "LEDCHIPLED_0805")
      (footprint "eagle-import:CHIPLED_0805")
      (libsource (lib "eagle-import") (part "LEDCHIPLED_0805"))
    )
    (comp (ref "LED14")
      (value "LEDCHIPLED_0805")
      (footprint "eagle-import:CHIPLED_0805")
      (libsource (lib "eagle-import") (part "LEDCHIPLED_0805"))
    )
    (comp (ref "LED15")
      (value "LEDCHIPLED_0805")
      (footprint "eagle-import:CHIPLED_0805")
      (libsource (lib "eagle-import") (part "LEDCHIPLED_0805"))
    )
    (comp (ref "R4")
      (value "1k")
      (footprint "eagle-import:R0805")
      (libsource (lib "eagle-import") (part "R-EU_R0805"))
    )
    (comp (ref "R18")
      (value "1k")
      (footprint "eagle-import:R0805")
      (libsource (lib "eagle-import") (part "R-EU_R0805"))
    )
    (comp (ref "R20")
      (value "100k")
      (footprint "eagle-import:R0805")
      (libsource (lib "eagle-import") (part "R-EU_R0805"))
    )
    (comp (ref "R29")
      (value "1k")
      (footprint "eagle-import:R0805")
      (libsource (lib "eagle-import") (part "R-EU_R0805"))
    )
    (comp (ref "R30")
      (value "1k")
      (footprint "eagle-import:R0805")
      (libsource (lib "eagle-import") (part "R-EU_R0805"))
    )
    (comp (ref "R69")
      (value "1k")
      (footprint "eagle-import:R0805")
      (libsource (lib "eagle-import") (part "R-EU_R0805"))
    )
    (comp (ref "R70")
      (value "1k")
      (footprint "eagle-import:R0805")
      (libsource (lib "eagle-import") (part "R-EU_R0805"))
    )
    (comp (ref "R71")
      (value "100k")
      (footprint "eagle-import:R0805")
      (libsource (lib "eagle-import") (part "R-EU_R0805"))
    )
    (comp (ref "SJ5") (value "SJ") (footprint "eagle-import:SJ") (libsource (lib "eagle-import") (part "SJ")))
    (comp (ref "SJ12")
      (value "SJ")
      (footprint "eagle-import:SJ")
      (libsource (lib "eagle-import") (part "SJ"))
    )
    (comp (ref "SJ13")
      (value "SJ")
      (footprint "eagle-import:SJ")
      (libsource (lib "eagle-import") (part "SJ"))
    )
    (comp (ref "SJ14")
      (value "SJ")
      (footprint "eagle-import:SJ")
      (libsource (lib "eagle-import") (part "SJ"))
    )
    (comp (ref "SJ15")
      (value "SJ")
      (footprint "eagle-import:SJ")
      (libsource (lib "eagle-import") (part "SJ"))
    )
    (comp (ref "TP5")
      (value "PAD´S8")
      (footprint "eagle-import:THT-1X2,54")
      (libsource (lib "eagle-import") (part "PAD´S8"))
    )
    (comp (ref "TP6")
      (value "PAD´S8")
      (footprint "eagle-import:THT-1X2,54")
      (libsource (lib "eagle-import") (part "PAD´S8"))
    )
    (comp (ref "TP7")
      (value "PAD´S8")
      (footprint "eagle-import:THT-1X2,54")
      (libsource (lib "eagle-import") (part "PAD´S8"))
    )
    (comp (ref "TP14")
      (value "PAD´S8")
      (footprint "eagle-import:THT-1X2,54")
      (libsource (lib "eagle-import") (part "PAD´S8"))
    )
    (comp (ref "TP15")
      (value "PAD´S8")
      (footprint "eagle-import:THT-1X2,54")
      (libsource (lib "eagle-import") (part "PAD´S8"))
    )
    (comp (ref "TP17")
      (value "PAD´S8")
      (footprint "eagle-import:THT-1X2,54")
      (libsource (lib "eagle-import") (part "PAD´S8"))
    )
    (comp (ref "TP18")
      (value "PAD´S8")
      (footprint "eagle-import:THT-1X2,54")
      (libsource (lib "eagle-import") (part "PAD´S8"))
    )
  )
  (nets
    (net (code "1") (name "+3V3") (class "Default")
      (node (ref "A1") (pin "+") (pinfunction "+_+") (pintype "power_in"))
      (node (ref "C14") (pin "2") (pinfunction "2_2") (pintype "passive"))
      (node (ref "C23") (pin "+") (pinfunction "+_+") (pintype "passive"))
      (node (ref "C24") (pin "1") (pinfunction "1_1") (pintype "passive"))
      (node (ref "C8") (pin "1") (pinfunction "1_1") (pintype "passive"))
      (node (ref "C9") (pin "1") (pinfunction "1_1") (pintype "passive"))
      (node (ref "CON_DCF_2") (pin "1") (pinfunction "1_1") (pintype "passive"))
      (node (ref "CON_DCF_2") (pin "2") (pinfunction "2_2") (pintype "passive"))
      (node (ref "CON_TOUCH_SENSOR_2") (pin "6") (pinfunction "6_6") (pintype "passive"))
      (node (ref "D1") (pin "A") (pinfunction "A_A") (pintype "passive"))
      (node (ref "FFC1") (pin "11") (pinfunction "11_11") (pintype "passive"))
      (node (ref "FFC1") (pin "13") (pinfunction "13_13") (pintype "passive"))
      (node (ref "FFC1") (pin "15") (pinfunction "15_15") (pintype "passive"))
      (node (ref "FFC1") (pin "9") (pinfunction "9_9") (pintype "passive"))
      (node (ref "IC3") (pin "21") (pinfunction "VDD_21") (pintype "bidirectional"))
      (node (ref "IC3") (pin "38") (pinfunction "LED_VDD_38") (pintype "input"))
      (node (ref "IC3") (pin "7") (pinfunction "LED_VDD_7") (pintype "input"))
      (node (ref "IC4") (pin "4") (pinfunction "VOUT_4") (pintype "bidirectional"))
      (node (ref "IC8") (pin "17") (pinfunction "VCC1_17") (pintype "power_in"))
      (node (ref "IC8") (pin "38") (pinfunction "VCC2_38") (pintype "power_in"))
      (node (ref "IC8") (pin "5") (pinfunction "VCC_5") (pintype "power_in"))
      (node (ref "IC9") (pin "1") (pinfunction "VIN_1") (pintype "bidirectional"))
      (node (ref "LED2") (pin "A") (pinfunction "A_A") (pintype "passive"))
      (node (ref "LED7") (pin "A") (pinfunction "A_A") (pintype "passive"))
      (node (ref "R13") (pin "1") (pinfunction "1_1") (pintype "passive"))
      (node (ref "R15") (pin "1") (pinfunction "1_1") (pintype "passive"))
      (node (ref "R20") (pin "2") (pinfunction "2_2") (pintype "passive"))
      (node (ref "R26") (pin "2") (pinfunction "2_2") (pintype "passive"))
      (node (ref "R27") (pin "2") (pinfunction "2_2") (pintype "passive"))
      (node (ref "R3") (pin "1") (pinfunction "1_1") (pintype "passive"))
      (node (ref "R7") (pin "2") (pinfunction "2_2") (pintype "passive"))
      (node (ref "SJ3") (pin "2") (pinfunction "2_2") (pintype "passive"))
      (node (ref "SJ4") (pin "2") (pinfunction "2_2") (pintype "passive"))
      (node (ref "TP8") (pin "TP") (pinfunction "TP_TP") (pintype "bidirectional"))
      (node (ref "XW1") (pin "2") (pinfunction "VCC_2") (pintype "power_in"))
    )
    (net (code "2") (name "+3V3_TOUCH_SENSOR_MODUL") (class "Default")
      (node (ref "C2") (pin "1") (pinfunction "1_1") (pintype "passive"))
      (node (ref "CON_TOUCH_SENSOR_1") (pin "1") (pinfunction "1_1") (pintype "passive"))
      (node (ref "IC6") (pin "9") (pinfunction "VDD_9") (pintype "bidirectional"))
      (node (ref "R16") (pin "2") (pinfunction "2_2") (pintype "passive"))
      (node (ref "R6") (pin "2") (pinfunction "2_2") (pintype "passive"))
      (node (ref "SJ6") (pin "2") (pinfunction "2_2") (pintype "passive"))
      (node (ref "SJ7") (pin "2") (pinfunction "2_2") (pintype "passive"))
      (node (ref "TP19") (pin "TP") (pinfunction "TP_TP") (pintype "bidirectional"))
    )
    (net (code "3") (name "ABORT_ALL_FUNCTIONS") (class "Default")
      (node (ref "C19") (pin "1") (pinfunction "1_1") (pintype "passive"))
      (node (ref "FFC2") (pin "1") (pinfunction "1_1") (pintype "passive"))
      (node (ref "R25") (pin "2") (pinfunction "2_2") (pintype "passive"))
      (node (ref "T5") (pin "1") (pinfunction "1_1") (pintype "bidirectional"))
      (node (ref "T5") (pin "2") (pinfunction "2_2") (pintype "bidirectional"))
    )
    (net (code "4") (name "ABORT_ALL_FUNCTIONS_TO_CONNECTOR") (class "Default")
      (node (ref "D2") (pin "C") (pinfunction "C_C") (pintype "passive"))
      (node (ref "FFC1") (pin "16") (pinfunction "16_16") (pintype "passive"))
      (node (ref "IC8") (pin "25") (pinfunction "(TOSC1)PC6_25") (pintype "bidirectional"))
    )
    (net (code "5") (name "CHANGE_INT_TOUCH") (class "Default")
      (node (ref "CON_TOUCH_SENSOR_1") (pin "2") (pinfunction "2_2") (pintype "passive"))
      (node (ref "IC6") (pin "15") (pinfunction "CHANGE_15") (pintype "bidirectional"))
      (node (ref "R6") (pin "1") (pinfunction "1_1") (pintype "passive"))
    )
    (net (code "6") (name "CLKOUT") (class "Default")
      (node (ref "IC2") (pin "5") (pinfunction "CLKOUT_5") (pintype "output"))
      (node (ref "R18") (pin "1") (pinfunction "1_1") (pintype "passive"))
    )
    (net (code "7") (name "COL_0") (class "Default")
      (node (ref "DIS1") (pin "1") (pinfunction "1_1") (pintype "input"))
      (node (ref "DIS2") (pin "1") (pinfunction "1_1") (pintype "input"))
      (node (ref "DIS3") (pin "1") (pinfunction "1_1") (pintype "input"))
      (node (ref "DIS4") (pin "1") (pinfunction "1_1") (pintype "input"))
      (node (ref "IC3") (pin "22") (pinfunction "COM0_22") (pintype "bidirectional"))
    )
    (net (code "8") (name "COL_1") (class "Default")
      (node (ref "DIS1") (pin "2") (pinfunction "2_2") (pintype "input"))
      (node (ref "DIS2") (pin "2") (pinfunction "2_2") (pintype "input"))
      (node (ref "DIS3") (pin "2") (pinfunction "2_2") (pintype "input"))
      (node (ref "DIS4") (pin "2") (pinfunction "2_2") (pintype "input"))
      (node (ref "IC3") (pin "23") (pinfunction "COM1_23") (pintype "bidirectional"))
    )
    (net (code "9") (name "COL_2") (class "Default")
      (node (ref "DIS1") (pin "3") (pinfunction "3_3") (pintype "input"))
      (node (ref "DIS2") (pin "3") (pinfunction "3_3") (pintype "input"))
      (node (ref "DIS3") (pin "3") (pinfunction "3_3") (pintype "input"))
      (node (ref "DIS4") (pin "3") (pinfunction "3_3") (pintype "input"))
      (node (ref "IC3") (pin "24") (pinfunction "COM2_24") (pintype "bidirectional"))
    )
    (net (code "10") (name "COL_3") (class "Default")
      (node (ref "DIS1") (pin "4") (pinfunction "4_4") (pintype "input"))
      (node (ref "DIS2") (pin "4") (pinfunction "4_4") (pintype "input"))
      (node (ref "DIS3") (pin "4") (pinfunction "4_4") (pintype "input"))
      (node (ref "DIS4") (pin "4") (pinfunction "4_4") (pintype "input"))
      (node (ref "IC3") (pin "26") (pinfunction "COM3_26") (pintype "bidirectional"))
    )
    (net (code "11") (name "COL_4") (class "Default")
      (node (ref "DIS1") (pin "12") (pinfunction "12_12") (pintype "input"))
      (node (ref "DIS2") (pin "12") (pinfunction "12_12") (pintype "input"))
      (node (ref "DIS3") (pin "12") (pinfunction "12_12") (pintype "input"))
      (node (ref "DIS4") (pin "12") (pinfunction "12_12") (pintype "input"))
      (node (ref "IC3") (pin "27") (pinfunction "COM4_27") (pintype "bidirectional"))
    )
    (net (code "12") (name "COL_5") (class "Default")
      (node (ref "DIS1") (pin "11") (pinfunction "11_11") (pintype "input"))
      (node (ref "DIS2") (pin "11") (pinfunction "11_11") (pintype "input"))
      (node (ref "DIS3") (pin "11") (pinfunction "11_11") (pintype "input"))
      (node (ref "DIS4") (pin "11") (pinfunction "11_11") (pintype "input"))
      (node (ref "IC3") (pin "28") (pinfunction "COM5_28") (pintype "bidirectional"))
    )
    (net (code "13") (name "COL_6") (class "Default")
      (node (ref "DIS1") (pin "10") (pinfunction "10_10") (pintype "input"))
      (node (ref "DIS2") (pin "10") (pinfunction "10_10") (pintype "input"))
      (node (ref "DIS3") (pin "10") (pinfunction "10_10") (pintype "input"))
      (node (ref "DIS4") (pin "10") (pinfunction "10_10") (pintype "input"))
      (node (ref "IC3") (pin "29") (pinfunction "COM6_29") (pintype "bidirectional"))
    )
    (net (code "14") (name "COL_7") (class "Default")
      (node (ref "DIS1") (pin "9") (pinfunction "9_9") (pintype "input"))
      (node (ref "DIS2") (pin "9") (pinfunction "9_9") (pintype "input"))
      (node (ref "DIS3") (pin "9") (pinfunction "9_9") (pintype "input"))
      (node (ref "DIS4") (pin "9") (pinfunction "9_9") (pintype "input"))
      (node (ref "IC3") (pin "30") (pinfunction "COM7_30") (pintype "bidirectional"))
    )
    (net (code "15") (name "CP2102_RESET") (class "Default")
      (node (ref "IC1") (pin "9") (pinfunction "RESET_9") (pintype "bidirectional"))
      (node (ref "R28") (pin "2") (pinfunction "2_2") (pintype "passive"))
    )
    (net (code "16") (name "CP2102_RXD") (class "Default")
      (node (ref "IC1") (pin "25") (pinfunction "RXD_25") (pintype "bidirectional"))
      (node (ref "IC8") (pin "10") (pinfunction "(TXD)PD1_10") (pintype "bidirectional"))
    )
    (net (code "17") (name "CP2102_TXD") (class "Default")
      (node (ref "IC1") (pin "26") (pinfunction "TXD_26") (pintype "bidirectional"))
      (node (ref "IC8") (pin "9") (pinfunction "(RXD)PD0_9") (pintype "bidirectional"))
    )
    (net (code "18") (name "D+") (class "Default")
      (node (ref "IC1") (pin "4") (pinfunction "D+_4") (pintype "bidirectional"))
      (node (ref "IC11") (pin "3") (pinfunction "IO1_3") (pintype "bidirectional"))
      (node (ref "POWER_CON_2") (pin "5") (pinfunction "5_5") (pintype "passive"))
    )
    (net (code "19") (name "D-") (class "Default")
      (node (ref "IC1") (pin "5") (pinfunction "D-_5") (pintype "bidirectional"))
      (node (ref "IC11") (pin "6") (pinfunction "IO2_6") (pintype "bidirectional"))
      (node (ref "POWER_CON_2") (pin "2") (pinfunction "2_2") (pintype "passive"))
    )
    (net (code "20") (name "D1_ROW0") (class "Default")
      (node (ref "DIS1") (pin "16") (pinfunction "16_16") (pintype "input"))
      (node (ref "R62") (pin "1") (pinfunction "1_1") (pintype "passive"))
    )
    (net (code "21") (name "D1_ROW1") (class "Default")
      (node (ref "DIS1") (pin "15") (pinfunction "15_15") (pintype "input"))
      (node (ref "R63") (pin "1") (pinfunction "1_1") (pintype "passive"))
    )
    (net (code "22") (name "D1_ROW2") (class "Default")
      (node (ref "DIS1") (pin "14") (pinfunction "14_14") (pintype "input"))
      (node (ref "R65") (pin "1") (pinfunction "1_1") (pintype "passive"))
    )
    (net (code "23") (name "D1_ROW3") (class "Default")
      (node (ref "DIS1") (pin "13") (pinfunction "13_13") (pintype "input"))
      (node (ref "R66") (pin "1") (pinfunction "1_1") (pintype "passive"))
    )
    (net (code "24") (name "D1_ROW4") (class "Default")
      (node (ref "DIS1") (pin "5") (pinfunction "5_5") (pintype "input"))
      (node (ref "R67") (pin "1") (pinfunction "1_1") (pintype "passive"))
    )
    (net (code "25") (name "D1_ROW5") (class "Default")
      (node (ref "DIS1") (pin "6") (pinfunction "6_6") (pintype "input"))
      (node (ref "R74") (pin "1") (pinfunction "1_1") (pintype "passive"))
    )
    (net (code "26") (name "D1_ROW6") (class "Default")
      (node (ref "DIS1") (pin "7") (pinfunction "7_7") (pintype "input"))
      (node (ref "R75") (pin "1") (pinfunction "1_1") (pintype "passive"))
    )
    (net (code "27") (name "D1_ROW7") (class "Default")
      (node (ref "DIS1") (pin "8") (pinfunction "8_8") (pintype "input"))
      (node (ref "R76") (pin "1") (pinfunction "1_1") (pintype "passive"))
    )
    (net (code "28") (name "D2_ROW0") (class "Default")
      (node (ref "DIS2") (pin "16") (pinfunction "16_16") (pintype "input"))
      (node (ref "R77") (pin "1") (pinfunction "1_1") (pintype "passive"))
    )
    (net (code "29") (name "D2_ROW1") (class "Default")
      (node (ref "DIS2") (pin "15") (pinfunction "15_15") (pintype "input"))
      (node (ref "R78") (pin "1") (pinfunction "1_1") (pintype "passive"))
    )
    (net (code "30") (name "D2_ROW2") (class "Default")
      (node (ref "DIS2") (pin "14") (pinfunction "14_14") (pintype "input"))
      (node (ref "R79") (pin "1") (pinfunction "1_1") (pintype "passive"))
    )
    (net (code "31") (name "D2_ROW3") (class "Default")
      (node (ref "DIS2") (pin "13") (pinfunction "13_13") (pintype "input"))
      (node (ref "R80") (pin "1") (pinfunction "1_1") (pintype "passive"))
    )
    (net (code "32") (name "D2_ROW4") (class "Default")
      (node (ref "DIS2") (pin "5") (pinfunction "5_5") (pintype "input"))
      (node (ref "R81") (pin "1") (pinfunction "1_1") (pintype "passive"))
    )
    (net (code "33") (name "D2_ROW5") (class "Default")
      (node (ref "DIS2") (pin "6") (pinfunction "6_6") (pintype "input"))
      (node (ref "R82") (pin "1") (pinfunction "1_1") (pintype "passive"))
    )
    (net (code "34") (name "D2_ROW6") (class "Default")
      (node (ref "DIS2") (pin "7") (pinfunction "7_7") (pintype "input"))
      (node (ref "R83") (pin "1") (pinfunction "1_1") (pintype "passive"))
    )
    (net (code "35") (name "D2_ROW7") (class "Default")
      (node (ref "DIS2") (pin "8") (pinfunction "8_8") (pintype "input"))
      (node (ref "R84") (pin "1") (pinfunction "1_1") (pintype "passive"))
    )
    (net (code "36") (name "D3_ROW0") (class "Default")
      (node (ref "DIS3") (pin "16") (pinfunction "16_16") (pintype "input"))
      (node (ref "R85") (pin "1") (pinfunction "1_1") (pintype "passive"))
    )
    (net (code "37") (name "D3_ROW1") (class "Default")
      (node (ref "DIS3") (pin "15") (pinfunction "15_15") (pintype "input"))
      (node (ref "R86") (pin "1") (pinfunction "1_1") (pintype "passive"))
    )
    (net (code "38") (name "D3_ROW2") (class "Default")
      (node (ref "DIS3") (pin "14") (pinfunction "14_14") (pintype "input"))
      (node (ref "R87") (pin "1") (pinfunction "1_1") (pintype "passive"))
    )
    (net (code "39") (name "D3_ROW3") (class "Default")
      (node (ref "DIS3") (pin "13") (pinfunction "13_13") (pintype "input"))
      (node (ref "R88") (pin "1") (pinfunction "1_1") (pintype "passive"))
    )
    (net (code "40") (name "D3_ROW4") (class "Default")
      (node (ref "DIS3") (pin "5") (pinfunction "5_5") (pintype "input"))
      (node (ref "R89") (pin "1") (pinfunction "1_1") (pintype "passive"))
    )
    (net (code "41") (name "D3_ROW5") (class "Default")
      (node (ref "DIS3") (pin "6") (pinfunction "6_6") (pintype "input"))
      (node (ref "R90") (pin "1") (pinfunction "1_1") (pintype "passive"))
    )
    (net (code "42") (name "D3_ROW6") (class "Default")
      (node (ref "DIS3") (pin "7") (pinfunction "7_7") (pintype "input"))
      (node (ref "R91") (pin "1") (pinfunction "1_1") (pintype "passive"))
    )
    (net (code "43") (name "D3_ROW7") (class "Default")
      (node (ref "DIS3") (pin "8") (pinfunction "8_8") (pintype "input"))
      (node (ref "R92") (pin "1") (pinfunction "1_1") (pintype "passive"))
    )
    (net (code "44") (name "D4_ROW0") (class "Default")
      (node (ref "DIS4") (pin "16") (pinfunction "16_16") (pintype "input"))
      (node (ref "R93") (pin "1") (pinfunction "1_1") (pintype "passive"))
    )
    (net (code "45") (name "D4_ROW1") (class "Default")
      (node (ref "DIS4") (pin "15") (pinfunction "15_15") (pintype "input"))
      (node (ref "R94") (pin "1") (pinfunction "1_1") (pintype "passive"))
    )
    (net (code "46") (name "D4_ROW2") (class "Default")
      (node (ref "DIS4") (pin "14") (pinfunction "14_14") (pintype "input"))
      (node (ref "R95") (pin "1") (pinfunction "1_1") (pintype "passive"))
    )
    (net (code "47") (name "D4_ROW3") (class "Default")
      (node (ref "DIS4") (pin "13") (pinfunction "13_13") (pintype "input"))
      (node (ref "R96") (pin "1") (pinfunction "1_1") (pintype "passive"))
    )
    (net (code "48") (name "D4_ROW4") (class "Default")
      (node (ref "DIS4") (pin "5") (pinfunction "5_5") (pintype "input"))
      (node (ref "R97") (pin "1") (pinfunction "1_1") (pintype "passive"))
    )
    (net (code "49") (name "D4_ROW5") (class "Default")
      (node (ref "DIS4") (pin "6") (pinfunction "6_6") (pintype "input"))
      (node (ref "R98") (pin "1") (pinfunction "1_1") (pintype "passive"))
    )
    (net (code "50") (name "D4_ROW6") (class "Default")
      (node (ref "DIS4") (pin "7") (pinfunction "7_7") (pintype "input"))
      (node (ref "R99") (pin "1") (pinfunction "1_1") (pintype "passive"))
    )
    (net (code "51") (name "D4_ROW7") (class "Default")
      (node (ref "DIS4") (pin "8") (pinfunction "8_8") (pintype "input"))
      (node (ref "R100") (pin "1") (pinfunction "1_1") (pintype "passive"))
    )
    (net (code "52") (name "DCF77_buffFERED_INVERTED_FROM_DCF77_MODUL") (class "Default")
      (node (ref "CON_DCF_2") (pin "3") (pinfunction "3_3") (pintype "passive"))
      (node (ref "CON_DCF_2") (pin "4") (pinfunction "4_4") (pintype "passive"))
      (node (ref "IC8") (pin "42") (pinfunction "(AIN0/INT2)PB2_42") (pintype "bidirectional"))
    )
    (net (code "53") (name "ENCODER_A") (class "Default")
      (node (ref "C15") (pin "1") (pinfunction "1_1") (pintype "passive"))
      (node (ref "ENC1") (pin "A") (pinfunction "A_A") (pintype "bidirectional"))
      (node (ref "ENC2") (pin "4") (pinfunction "4_4") (pintype "output"))
      (node (ref "FFC2") (pin "15") (pinfunction "15_15") (pintype "passive"))
      (node (ref "R22") (pin "1") (pinfunction "1_1") (pintype "passive"))
    )
    (net (code "54") (name "ENCODER_A_TO_CONNECTOR") (class "Default")
      (node (ref "FFC1") (pin "2") (pinfunction "2_2") (pintype "passive"))
      (node (ref "IC8") (pin "16") (pinfunction "(OC2)PD7_16") (pintype "bidirectional"))
    )
    (net (code "55") (name "ENCODER_B") (class "Default")
      (node (ref "C16") (pin "1") (pinfunction "1_1") (pintype "passive"))
      (node (ref "ENC1") (pin "B") (pinfunction "B_B") (pintype "bidirectional"))
      (node (ref "ENC2") (pin "3") (pinfunction "3_3") (pintype "output"))
      (node (ref "FFC2") (pin "13") (pinfunction "13_13") (pintype "passive"))
      (node (ref "R23") (pin "1") (pinfunction "1_1") (pintype "passive"))
    )
    (net (code "56") (name "ENCODER_B_TO_CONNECTOR") (class "Default")
      (node (ref "FFC1") (pin "4") (pinfunction "4_4") (pintype "passive"))
      (node (ref "IC8") (pin "15") (pinfunction "(ICP)PD6_15") (pintype "bidirectional"))
    )
    (net (code "57") (name "GND") (class "Default")
      (node (ref "C1") (pin "2") (pinfunction "2_2") (pintype "passive"))
      (node (ref "C14") (pin "1") (pinfunction "1_1") (pintype "passive"))
      (node (ref "C17") (pin "2") (pinfunction "2_2") (pintype "passive"))
      (node (ref "C20") (pin "2") (pinfunction "2_2") (pintype "passive"))
      (node (ref "C21") (pin "2") (pinfunction "2_2") (pintype "passive"))
      (node (ref "C22") (pin "-") (pinfunction "-_-") (pintype "passive"))
      (node (ref "C23") (pin "-") (pinfunction "-_-") (pintype "passive"))
      (node (ref "C24") (pin "2") (pinfunction "2_2") (pintype "passive"))
      (node (ref "C29") (pin "-") (pinfunction "-_-") (pintype "passive"))
      (node (ref "C3") (pin "2") (pinfunction "2_2") (pintype "passive"))
      (node (ref "C30") (pin "-") (pinfunction "-_-") (pintype "passive"))
      (node (ref "C31") (pin "MINUS") (pinfunction "-_MINUS") (pintype "passive"))
      (node (ref "C4") (pin "2") (pinfunction "2_2") (pintype "passive"))
      (node (ref "C5") (pin "2") (pinfunction "2_2") (pintype "passive"))
      (node (ref "C6") (pin "2") (pinfunction "2_2") (pintype "passive"))
      (node (ref "C7") (pin "2") (pinfunction "2_2") (pintype "passive"))
      (node (ref "C8") (pin "2") (pinfunction "2_2") (pintype "passive"))
      (node (ref "C9") (pin "2") (pinfunction "2_2") (pintype "passive"))
      (node (ref "CON_DCF_2") (pin "5") (pinfunction "5_5") (pintype "passive"))
      (node (ref "CON_DCF_2") (pin "6") (pinfunction "6_6") (pintype "passive"))
      (node (ref "CON_TOUCH_SENSOR_2") (pin "1") (pinfunction "1_1") (pintype "passive"))
      (node (ref "CON_TOUCH_SENSOR_2") (pin "2") (pinfunction "2_2") (pintype "passive"))
      (node (ref "FFC1") (pin "1") (pinfunction "1_1") (pintype "passive"))
      (node (ref "FFC1") (pin "3") (pinfunction "3_3") (pintype "passive"))
      (node (ref "FFC1") (pin "5") (pinfunction "5_5") (pintype "passive"))
      (node (ref "FFC1") (pin "7") (pinfunction "7_7") (pintype "passive"))
      (node (ref "IC1") (pin "3") (pinfunction "GND_3") (pintype "bidirectional"))
      (node (ref "IC1") (pin "THERMAL") (pinfunction "GND_THERMAL") (pintype "bidirectional"))
      (node (ref "IC11") (pin "4") (pinfunction "GND_4") (pintype "bidirectional"))
      (node (ref "IC11") (pin "THERMAL") (pinfunction "GND_THERMAL") (pintype "bidirectional"))
      (node (ref "IC2") (pin "8") (pinfunction "GND_8") (pintype "power_in"))
      (node (ref "IC2") (pin "9") (pinfunction "GND_9") (pintype "power_in"))
      (node (ref "IC3") (pin "14") (pinfunction "VSS_14") (pintype "bidirectional"))
      (node (ref "IC3") (pin "25") (pinfunction "LED_VSS_25") (pintype "input"))
      (node (ref "IC3") (pin "36") (pinfunction "LED_VSS_36") (pintype "input"))
      (node (ref "IC4") (pin "2") (pinfunction "GND_2") (pintype "bidirectional"))
      (node (ref "IC4") (pin "EXP") (pinfunction "GND_EXP") (pintype "bidirectional"))
      (node (ref "IC5") (pin "4") (pinfunction "S_4") (pintype "passive"))
      (node (ref "IC7") (pin "4") (pinfunction "S_4") (pintype "passive"))
      (node (ref "IC8") (pin "18") (pinfunction "GND1_18") (pintype "power_in"))
      (node (ref "IC8") (pin "28") (pinfunction "GND_28") (pintype "power_in"))
      (node (ref "IC8") (pin "39") (pinfunction "GND2_39") (pintype "power_in"))
      (node (ref "IC8") (pin "6") (pinfunction "GND_6") (pintype "power_in"))
      (node (ref "IC9") (pin "2") (pinfunction "GND_2") (pintype "bidirectional"))
      (node (ref "POWER_CON_2") (pin "4") (pinfunction "4_4") (pintype "passive"))
      (node (ref "POWER_CON_2") (pin "6") (pinfunction "6_6") (pintype "passive"))
      (node (ref "R11") (pin "2") (pinfunction "2_2") (pintype "passive"))
      (node (ref "R14") (pin "2") (pinfunction "2_2") (pintype "passive"))
      (node (ref "R2") (pin "2") (pinfunction "2_2") (pintype "passive"))
      (node (ref "TP9") (pin "TP") (pinfunction "TP_TP") (pintype "bidirectional"))
      (node (ref "XW1") (pin "6") (pinfunction "GND_6") (pintype "power_in"))
    )
    (net (code "58") (name "GND_DCF77") (class "Default")
      (node (ref "A3") (pin "1") (pinfunction "GND_1") (pintype "bidirectional"))
      (node (ref "C11") (pin "2") (pinfunction "2_2") (pintype "passive"))
      (node (ref "C25") (pin "2") (pinfunction "2_2") (pintype "passive"))
      (node (ref "C26") (pin "2") (pinfunction "2_2") (pintype "passive"))
      (node (ref "CON_DCF_1") (pin "1") (pinfunction "1_1") (pintype "passive"))
      (node (ref "CON_DCF_1") (pin "2") (pinfunction "2_2") (pintype "passive"))
      (node (ref "IC10") (pin "7") (pinfunction "VSS_7") (pintype "power_in"))
      (node (ref "TP14") (pin "TP") (pinfunction "TP_TP") (pintype "bidirectional"))
    )
    (net (code "59") (name "GND_SWITCHBOARD") (class "Default")
      (node (ref "C10") (pin "2") (pinfunction "2_2") (pintype "passive"))
      (node (ref "C12") (pin "2") (pinfunction "2_2") (pintype "passive"))
      (node (ref "C15") (pin "2") (pinfunction "2_2") (pintype "passive"))
      (node (ref "C16") (pin "2") (pinfunction "2_2") (pintype "passive"))
      (node (ref "C18") (pin "2") (pinfunction "2_2") (pintype "passive"))
      (node (ref "C19") (pin "2") (pinfunction "2_2") (pintype "passive"))
      (node (ref "C27") (pin "2") (pinfunction "2_2") (pintype "passive"))
      (node (ref "C28") (pin "2") (pinfunction "2_2") (pintype "passive"))
      (node (ref "ENC1") (pin "C") (pinfunction "C_C") (pintype "bidirectional"))
      (node (ref "ENC1") (pin "E") (pinfunction "E_E") (pintype "bidirectional"))
      (node (ref "ENC1") (pin "SHIELD_1") (pinfunction "SHIELD_1_SHIELD_1") (pintype "bidirectional"))
      (node (ref "ENC1") (pin "SHIELD_2") (pinfunction "SHIELD_1_SHIELD_2") (pintype "bidirectional"))
      (node (ref "ENC1") (pin "SHIELD_3") (pinfunction "SHIELD_1_SHIELD_3") (pintype "bidirectional"))
      (node (ref "ENC1") (pin "SHIELD_4") (pinfunction "SHIELD_1_SHIELD_4") (pintype "bidirectional"))
      (node (ref "ENC1") (pin "SHIELD_5") (pinfunction "SHIELD_1_SHIELD_5") (pintype "bidirectional"))
      (node (ref "ENC1") (pin "SHIELD_6") (pinfunction "SHIELD_1_SHIELD_6") (pintype "bidirectional"))
      (node (ref "ENC2") (pin "2") (pinfunction "2_2") (pintype "input"))
      (node (ref "ENC2") (pin "5") (pinfunction "1_5") (pintype "bidirectional"))
      (node (ref "FFC2") (pin "10") (pinfunction "10_10") (pintype "passive"))
      (node (ref "FFC2") (pin "12") (pinfunction "12_12") (pintype "passive"))
      (node (ref "FFC2") (pin "14") (pinfunction "14_14") (pintype "passive"))
      (node (ref "FFC2") (pin "16") (pinfunction "16_16") (pintype "passive"))
      (node (ref "T1") (pin "3") (pinfunction "3_3") (pintype "bidirectional"))
      (node (ref "T1") (pin "4") (pinfunction "4_4") (pintype "bidirectional"))
      (node (ref "T2") (pin "3") (pinfunction "3_3") (pintype "bidirectional"))
      (node (ref "T2") (pin "4") (pinfunction "4_4") (pintype "bidirectional"))
      (node (ref "T3") (pin "3") (pinfunction "3_3") (pintype "bidirectional"))
      (node (ref "T3") (pin "4") (pinfunction "4_4") (pintype "bidirectional"))
      (node (ref "T4") (pin "3") (pinfunction "3_3") (pintype "bidirectional"))
      (node (ref "T4") (pin "4") (pinfunction "4_4") (pintype "bidirectional"))
      (node (ref "T5") (pin "3") (pinfunction "3_3") (pintype "bidirectional"))
      (node (ref "T5") (pin "4") (pinfunction "4_4") (pintype "bidirectional"))
    )
    (net (code "60") (name "GND_TOUCH") (class "Default")
      (node (ref "C2") (pin "2") (pinfunction "2_2") (pintype "passive"))
      (node (ref "CON_TOUCH_SENSOR_1") (pin "5") (pinfunction "5_5") (pintype "passive"))
      (node (ref "CON_TOUCH_SENSOR_1") (pin "6") (pinfunction "6_6") (pintype "passive"))
      (node (ref "IC6") (pin "10") (pinfunction "MODE_10") (pintype "bidirectional"))
      (node (ref "IC6") (pin "8") (pinfunction "GND_8") (pintype "bidirectional"))
      (node (ref "IC6") (pin "EXP.") (pinfunction "GND_EXP.") (pintype "bidirectional"))
      (node (ref "TP20") (pin "TP") (pinfunction "TP_TP") (pintype "bidirectional"))
    )
    (net (code "61") (name "HEARTBEAT") (class "Default")
      (node (ref "IC8") (pin "13") (pinfunction "(OC1B)PD4_13") (pintype "bidirectional"))
      (node (ref "R5") (pin "1") (pinfunction "1_1") (pintype "passive"))
    )
    (net (code "62") (name "HT1632_CS") (class "Default")
      (node (ref "IC3") (pin "19") (pinfunction "CS_19") (pintype "input"))
      (node (ref "IC8") (pin "32") (pinfunction "(ADC5)PA5_32") (pintype "bidirectional"))
      (node (ref "TP1") (pin "TP") (pinfunction "TP_TP") (pintype "bidirectional"))
    )
    (net (code "63") (name "HT1632_DATA") (class "Default")
      (node (ref "IC3") (pin "16") (pinfunction "DATA_16") (pintype "bidirectional"))
      (node (ref "IC8") (pin "35") (pinfunction "(ADC2)PA2_35") (pintype "bidirectional"))
      (node (ref "TP4") (pin "TP") (pinfunction "TP_TP") (pintype "bidirectional"))
    )
    (net (code "64") (name "HT1632_OSC") (class "Default")
      (node (ref "IC3") (pin "15") (pinfunction "OSC_15") (pintype "bidirectional"))
      (node (ref "IC8") (pin "37") (pinfunction "(ADC0)PA0_37") (pintype "bidirectional"))
      (node (ref "TP11") (pin "TP") (pinfunction "TP_TP") (pintype "bidirectional"))
    )
    (net (code "65") (name "HT1632_RD") (class "Default")
      (node (ref "IC3") (pin "18") (pinfunction "RD_18") (pintype "input"))
      (node (ref "IC8") (pin "33") (pinfunction "(ADC4)PA4_33") (pintype "bidirectional"))
      (node (ref "TP2") (pin "TP") (pinfunction "TP_TP") (pintype "bidirectional"))
    )
    (net (code "66") (name "HT1632_SYNC") (class "Default")
      (node (ref "IC3") (pin "20") (pinfunction "SYNC_20") (pintype "input"))
      (node (ref "IC8") (pin "36") (pinfunction "(ADC1)PA1_36") (pintype "bidirectional"))
      (node (ref "TP16") (pin "TP") (pinfunction "TP_TP") (pintype "bidirectional"))
    )
    (net (code "67") (name "HT1632_WR") (class "Default")
      (node (ref "IC3") (pin "17") (pinfunction "WR_17") (pintype "input"))
      (node (ref "IC8") (pin "34") (pinfunction "(ADC3)PA3_34") (pintype "bidirectional"))
      (node (ref "TP3") (pin "TP") (pinfunction "TP_TP") (pintype "bidirectional"))
    )
    (net (code "68") (name "INTERRUPT_TOUCH_SENSOR") (class "Default")
      (node (ref "CON_TOUCH_SENSOR_2") (pin "5") (pinfunction "5_5") (pintype "passive"))
      (node (ref "D8") (pin "C") (pinfunction "C_C") (pintype "passive"))
    )
    (net (code "69") (name "LD39050-PG") (class "Default")
      (node (ref "IC4") (pin "3") (pinfunction "PG_3") (pintype "bidirectional"))
      (node (ref "IC8") (pin "31") (pinfunction "(ADC6)PA6_31") (pintype "bidirectional"))
      (node (ref "R15") (pin "2") (pinfunction "2_2") (pintype "passive"))
    )
    (net (code "70") (name "MISO") (class "Default")
      (node (ref "IC8") (pin "2") (pinfunction "(MISO)PB6_2") (pintype "bidirectional"))
      (node (ref "XW1") (pin "1") (pinfunction "MISO_1") (pintype "bidirectional"))
    )
    (net (code "71") (name "MOSI") (class "Default")
      (node (ref "IC8") (pin "1") (pinfunction "(MOSI)PB5_1") (pintype "bidirectional"))
      (node (ref "XW1") (pin "4") (pinfunction "MOSI_4") (pintype "bidirectional"))
    )
    (net (code "72") (name "Net-(A1-Pad-)") (class "Default")
      (node (ref "A1") (pin "-") (pinfunction "-_-") (pintype "power_in"))
      (node (ref "IC5") (pin "1") (pinfunction "D_1") (pintype "passive"))
      (node (ref "IC5") (pin "2") (pinfunction "D_2") (pintype "bidirectional"))
      (node (ref "IC5") (pin "5") (pinfunction "D_5") (pintype "bidirectional"))
      (node (ref "IC5") (pin "6") (pinfunction "D_6") (pintype "bidirectional"))
    )
    (net (code "73") (name "Net-(A3-DATA)") (class "Default")
      (node (ref "A3") (pin "2") (pinfunction "DATA_2") (pintype "bidirectional"))
      (node (ref "C26") (pin "1") (pinfunction "1_1") (pintype "passive"))
      (node (ref "IC10") (pin "1") (pinfunction "I0_1") (pintype "input"))
      (node (ref "IC10") (pin "2") (pinfunction "I1_2") (pintype "input"))
      (node (ref "SJ5") (pin "2") (pinfunction "2_2") (pintype "passive"))
      (node (ref "TP15") (pin "TP") (pinfunction "TP_TP") (pintype "bidirectional"))
    )
    (net (code "74") (name "Net-(CON_DCF_1-Pad3)") (class "Default")
      (node (ref "CON_DCF_1") (pin "3") (pinfunction "3_3") (pintype "passive"))
      (node (ref "CON_DCF_1") (pin "4") (pinfunction "4_4") (pintype "passive"))
      (node (ref "SJ12") (pin "1") (pinfunction "1_1") (pintype "passive"))
      (node (ref "SJ13") (pin "1") (pinfunction "1_1") (pintype "passive"))
    )
    (net (code "75") (name "Net-(D7-PadA)") (class "Default")
      (node (ref "D7") (pin "A") (pinfunction "A_A") (pintype "passive"))
      (node (ref "F2") (pin "2") (pinfunction "2_2") (pintype "passive"))
    )
    (net (code "76") (name "Net-(D10-PadA)") (class "Default")
      (node (ref "D10") (pin "A") (pinfunction "A_A") (pintype "passive"))
      (node (ref "D2") (pin "A") (pinfunction "A_A") (pintype "passive"))
      (node (ref "D3") (pin "A") (pinfunction "A_A") (pintype "passive"))
      (node (ref "D4") (pin "A") (pinfunction "A_A") (pintype "passive"))
      (node (ref "D5") (pin "A") (pinfunction "A_A") (pintype "passive"))
      (node (ref "D6") (pin "A") (pinfunction "A_A") (pintype "passive"))
      (node (ref "D8") (pin "A") (pinfunction "A_A") (pintype "passive"))
      (node (ref "R26") (pin "1") (pinfunction "1_1") (pintype "passive"))
      (node (ref "SJ2") (pin "2") (pinfunction "2_2") (pintype "passive"))
    )
    (net (code "77") (name "Net-(ENC2-Pad1)") (class "Default")
      (node (ref "ENC2") (pin "1") (pinfunction "1_1") (pintype "input"))
      (node (ref "R12") (pin "1") (pinfunction "1_1") (pintype "passive"))
    )
    (net (code "78") (name "Net-(F2-Pad1)") (class "Default")
      (node (ref "F2") (pin "1") (pinfunction "1_1") (pintype "passive"))
      (node (ref "POWER_CON_2") (pin "1") (pinfunction "1_1") (pintype "passive"))
      (node (ref "POWER_CON_2") (pin "3") (pinfunction "3_3") (pintype "passive"))
    )
    (net (code "79") (name "Net-(FFC2-Pad2)") (class "Default")
      (node (ref "FFC2") (pin "2") (pinfunction "2_2") (pintype "passive"))
      (node (ref "FFC2") (pin "4") (pinfunction "4_4") (pintype "passive"))
      (node (ref "FFC2") (pin "6") (pinfunction "6_6") (pintype "passive"))
      (node (ref "FFC2") (pin "8") (pinfunction "8_8") (pintype "passive"))
      (node (ref "R12") (pin "2") (pinfunction "2_2") (pintype "passive"))
      (node (ref "R22") (pin "2") (pinfunction "2_2") (pintype "passive"))
      (node (ref "R23") (pin "2") (pinfunction "2_2") (pintype "passive"))
      (node (ref "R24") (pin "2") (pinfunction "2_2") (pintype "passive"))
      (node (ref "R25") (pin "1") (pinfunction "1_1") (pintype "passive"))
      (node (ref "R64") (pin "1") (pinfunction "1_1") (pintype "passive"))
      (node (ref "R72") (pin "1") (pinfunction "1_1") (pintype "passive"))
      (node (ref "R8") (pin "1") (pinfunction "1_1") (pintype "passive"))
      (node (ref "R9") (pin "1") (pinfunction "1_1") (pintype "passive"))
    )
    (net (code "80") (name "Net-(IC1-VDD)") (class "Default")
      (node (ref "C21") (pin "1") (pinfunction "1_1") (pintype "passive"))
      (node (ref "IC1") (pin "6") (pinfunction "VDD_6") (pintype "bidirectional"))
      (node (ref "R28") (pin "1") (pinfunction "1_1") (pintype "passive"))
    )
    (net (code "81") (name "Net-(IC2-CLKOE)") (class "Default")
      (node (ref "IC2") (pin "3") (pinfunction "CLKOE_3") (pintype "input"))
      (node (ref "R4") (pin "1") (pinfunction "1_1") (pintype "passive"))
    )
    (net (code "82") (name "Net-(IC3-ROW0)") (class "Default")
      (node (ref "IC3") (pin "13") (pinfunction "ROW0_13") (pintype "bidirectional"))
      (node (ref "R62") (pin "2") (pinfunction "2_2") (pintype "passive"))
    )
    (net (code "83") (name "Net-(IC3-ROW1)") (class "Default")
      (node (ref "IC3") (pin "12") (pinfunction "ROW1_12") (pintype "bidirectional"))
      (node (ref "R63") (pin "2") (pinfunction "2_2") (pintype "passive"))
    )
    (net (code "84") (name "Net-(IC3-ROW2)") (class "Default")
      (node (ref "IC3") (pin "11") (pinfunction "ROW2_11") (pintype "bidirectional"))
      (node (ref "R65") (pin "2") (pinfunction "2_2") (pintype "passive"))
    )
    (net (code "85") (name "Net-(IC3-ROW3)") (class "Default")
      (node (ref "IC3") (pin "10") (pinfunction "ROW3_10") (pintype "bidirectional"))
      (node (ref "R66") (pin "2") (pinfunction "2_2") (pintype "passive"))
    )
    (net (code "86") (name "Net-(IC3-ROW4)") (class "Default")
      (node (ref "IC3") (pin "9") (pinfunction "ROW4_9") (pintype "bidirectional"))
      (node (ref "R67") (pin "2") (pinfunction "2_2") (pintype "passive"))
    )
    (net (code "87") (name "Net-(IC3-ROW5)") (class "Default")
      (node (ref "IC3") (pin "8") (pinfunction "ROW5_8") (pintype "bidirectional"))
      (node (ref "R74") (pin "2") (pinfunction "2_2") (pintype "passive"))
    )
    (net (code "88") (name "Net-(IC3-ROW6)") (class "Default")
      (node (ref "IC3") (pin "6") (pinfunction "ROW6_6") (pintype "bidirectional"))
      (node (ref "R75") (pin "2") (pinfunction "2_2") (pintype "passive"))
    )
    (net (code "89") (name "Net-(IC3-ROW7)") (class "Default")
      (node (ref "IC3") (pin "5") (pinfunction "ROW7_5") (pintype "bidirectional"))
      (node (ref "R76") (pin "2") (pinfunction "2_2") (pintype "passive"))
    )
    (net (code "90") (name "Net-(IC3-ROW8)") (class "Default")
      (node (ref "IC3") (pin "4") (pinfunction "ROW8_4") (pintype "output"))
      (node (ref "R77") (pin "2") (pinfunction "2_2") (pintype "passive"))
    )
    (net (code "91") (name "Net-(IC3-ROW9)") (class "Default")
      (node (ref "IC3") (pin "3") (pinfunction "ROW9_3") (pintype "output"))
      (node (ref "R78") (pin "2") (pinfunction "2_2") (pintype "passive"))
    )
    (net (code "92") (name "Net-(IC3-ROW10)") (class "Default")
      (node (ref "IC3") (pin "2") (pinfunction "ROW10_2") (pintype "output"))
      (node (ref "R79") (pin "2") (pinfunction "2_2") (pintype "passive"))
    )
    (net (code "93") (name "Net-(IC3-ROW11)") (class "Default")
      (node (ref "IC3") (pin "1") (pinfunction "ROW11_1") (pintype "output"))
      (node (ref "R80") (pin "2") (pinfunction "2_2") (pintype "passive"))
    )
    (net (code "94") (name "Net-(IC3-ROW12)") (class "Default")
      (node (ref "IC3") (pin "52") (pinfunction "ROW12_52") (pintype "output"))
      (node (ref "R81") (pin "2") (pinfunction "2_2") (pintype "passive"))
    )
    (net (code "95") (name "Net-(IC3-ROW13)") (class "Default")
      (node (ref "IC3") (pin "51") (pinfunction "ROW13_51") (pintype "output"))
      (node (ref "R82") (pin "2") (pinfunction "2_2") (pintype "passive"))
    )
    (net (code "96") (name "Net-(IC3-ROW14)") (class "Default")
      (node (ref "IC3") (pin "50") (pinfunction "ROW14_50") (pintype "output"))
      (node (ref "R83") (pin "2") (pinfunction "2_2") (pintype "passive"))
    )
    (net (code "97") (name "Net-(IC3-ROW15)") (class "Default")
      (node (ref "IC3") (pin "49") (pinfunction "ROW15_49") (pintype "output"))
      (node (ref "R84") (pin "2") (pinfunction "2_2") (pintype "passive"))
    )
    (net (code "98") (name "Net-(IC3-ROW16)") (class "Default")
      (node (ref "IC3") (pin "48") (pinfunction "ROW16_48") (pintype "bidirectional"))
      (node (ref "R85") (pin "2") (pinfunction "2_2") (pintype "passive"))
    )
    (net (code "99") (name "Net-(IC3-ROW17)") (class "Default")
      (node (ref "IC3") (pin "47") (pinfunction "ROW17_47") (pintype "bidirectional"))
      (node (ref "R86") (pin "2") (pinfunction "2_2") (pintype "passive"))
    )
    (net (code "100") (name "Net-(IC3-ROW18)") (class "Default")
      (node (ref "IC3") (pin "46") (pinfunction "ROW18_46") (pintype "bidirectional"))
      (node (ref "R87") (pin "2") (pinfunction "2_2") (pintype "passive"))
    )
    (net (code "101") (name "Net-(IC3-ROW19)") (class "Default")
      (node (ref "IC3") (pin "45") (pinfunction "ROW19_45") (pintype "bidirectional"))
      (node (ref "R88") (pin "2") (pinfunction "2_2") (pintype "passive"))
    )
    (net (code "102") (name "Net-(IC3-ROW20)") (class "Default")
      (node (ref "IC3") (pin "44") (pinfunction "ROW20_44") (pintype "bidirectional"))
      (node (ref "R89") (pin "2") (pinfunction "2_2") (pintype "passive"))
    )
    (net (code "103") (name "Net-(IC3-ROW21)") (class "Default")
      (node (ref "IC3") (pin "43") (pinfunction "ROW21_43") (pintype "bidirectional"))
      (node (ref "R90") (pin "2") (pinfunction "2_2") (pintype "passive"))
    )
    (net (code "104") (name "Net-(IC3-ROW22)") (class "Default")
      (node (ref "IC3") (pin "42") (pinfunction "ROW22_42") (pintype "bidirectional"))
      (node (ref "R91") (pin "2") (pinfunction "2_2") (pintype "passive"))
    )
    (net (code "105") (name "Net-(IC3-ROW23)") (class "Default")
      (node (ref "IC3") (pin "41") (pinfunction "ROW23_41") (pintype "bidirectional"))
      (node (ref "R92") (pin "2") (pinfunction "2_2") (pintype "passive"))
    )
    (net (code "106") (name "Net-(IC3-ROW24{slash}COM15)") (class "Default")
      (node (ref "IC3") (pin "40") (pinfunction "ROW24/COM15_40") (pintype "bidirectional"))
      (node (ref "R93") (pin "2") (pinfunction "2_2") (pintype "passive"))
    )
    (net (code "107") (name "Net-(IC3-ROW25{slash}COM14)") (class "Default")
      (node (ref "IC3") (pin "39") (pinfunction "ROW25/COM14_39") (pintype "bidirectional"))
      (node (ref "R94") (pin "2") (pinfunction "2_2") (pintype "passive"))
    )
    (net (code "108") (name "Net-(IC3-ROW26{slash}COM13)") (class "Default")
      (node (ref "IC3") (pin "37") (pinfunction "ROW26/COM13_37") (pintype "bidirectional"))
      (node (ref "R95") (pin "2") (pinfunction "2_2") (pintype "passive"))
    )
    (net (code "109") (name "Net-(IC3-ROW27{slash}COM12)") (class "Default")
      (node (ref "IC3") (pin "35") (pinfunction "ROW27/COM12_35") (pintype "bidirectional"))
      (node (ref "R96") (pin "2") (pinfunction "2_2") (pintype "passive"))
    )
    (net (code "110") (name "Net-(IC3-ROW28{slash}COM11)") (class "Default")
      (node (ref "IC3") (pin "34") (pinfunction "ROW28/COM11_34") (pintype "bidirectional"))
      (node (ref "R97") (pin "2") (pinfunction "2_2") (pintype "passive"))
    )
    (net (code "111") (name "Net-(IC3-ROW29{slash}COM10)") (class "Default")
      (node (ref "IC3") (pin "33") (pinfunction "ROW29/COM10_33") (pintype "bidirectional"))
      (node (ref "R98") (pin "2") (pinfunction "2_2") (pintype "passive"))
    )
    (net (code "112") (name "Net-(IC3-ROW30{slash}COM9)") (class "Default")
      (node (ref "IC3") (pin "32") (pinfunction "ROW30/COM9_32") (pintype "bidirectional"))
      (node (ref "R99") (pin "2") (pinfunction "2_2") (pintype "passive"))
    )
    (net (code "113") (name "Net-(IC3-ROW31{slash}COM8)") (class "Default")
      (node (ref "IC3") (pin "31") (pinfunction "ROW31/COM8_31") (pintype "bidirectional"))
      (node (ref "R100") (pin "2") (pinfunction "2_2") (pintype "passive"))
    )
    (net (code "114") (name "Net-(IC4-ADJ)") (class "Default")
      (node (ref "IC4") (pin "5") (pinfunction "ADJ_5") (pintype "bidirectional"))
      (node (ref "R13") (pin "2") (pinfunction "2_2") (pintype "passive"))
      (node (ref "R14") (pin "1") (pinfunction "1_1") (pintype "passive"))
    )
    (net (code "115") (name "Net-(IC4-EN)") (class "Default")
      (node (ref "IC4") (pin "1") (pinfunction "EN_1") (pintype "bidirectional"))
      (node (ref "R21") (pin "2") (pinfunction "2_2") (pintype "passive"))
    )
    (net (code "116") (name "Net-(IC5-G)") (class "Default")
      (node (ref "IC5") (pin "3") (pinfunction "G_3") (pintype "passive"))
      (node (ref "R10") (pin "1") (pinfunction "1_1") (pintype "passive"))
      (node (ref "R11") (pin "1") (pinfunction "1_1") (pintype "passive"))
    )
    (net (code "117") (name "Net-(IC6-KEY0)") (class "Default")
      (node (ref "IC6") (pin "7") (pinfunction "KEY0_7") (pintype "bidirectional"))
      (node (ref "TS1") (pin "GUARD") (pinfunction "GUARD_GUARD") (pintype "bidirectional"))
      (node (ref "TS2") (pin "GUARD") (pinfunction "GUARD_GUARD") (pintype "bidirectional"))
      (node (ref "TS3") (pin "GUARD") (pinfunction "GUARD_GUARD") (pintype "bidirectional"))
      (node (ref "TS4") (pin "GUARD") (pinfunction "GUARD_GUARD") (pintype "bidirectional"))
      (node (ref "TS5") (pin "GUARD") (pinfunction "GUARD_GUARD") (pintype "bidirectional"))
    )
    (net (code "118") (name "Net-(IC6-KEY1)") (class "Default")
      (node (ref "IC6") (pin "6") (pinfunction "KEY1_6") (pintype "bidirectional"))
      (node (ref "TS1") (pin "TOUCH") (pinfunction "TOUCH_TOUCH") (pintype "bidirectional"))
    )
    (net (code "119") (name "Net-(IC6-KEY2)") (class "Default")
      (node (ref "IC6") (pin "5") (pinfunction "KEY2_5") (pintype "bidirectional"))
      (node (ref "TS2") (pin "TOUCH") (pinfunction "TOUCH_TOUCH") (pintype "bidirectional"))
    )
    (net (code "120") (name "Net-(IC6-KEY3)") (class "Default")
      (node (ref "IC6") (pin "4") (pinfunction "KEY3_4") (pintype "bidirectional"))
      (node (ref "TS3") (pin "TOUCH") (pinfunction "TOUCH_TOUCH") (pintype "bidirectional"))
    )
    (net (code "121") (name "Net-(IC6-KEY4)") (class "Default")
      (node (ref "IC6") (pin "3") (pinfunction "KEY4_3") (pintype "bidirectional"))
      (node (ref "TS4") (pin "TOUCH") (pinfunction "TOUCH_TOUCH") (pintype "bidirectional"))
    )
    (net (code "122") (name "Net-(IC6-KEY5)") (class "Default")
      (node (ref "IC6") (pin "2") (pinfunction "KEY5_2") (pintype "bidirectional"))
      (node (ref "TS5") (pin "TOUCH") (pinfunction "TOUCH_TOUCH") (pintype "bidirectional"))
    )
    (net (code "123") (name "Net-(IC6-RESET)") (class "Default")
      (node (ref "IC6") (pin "12") (pinfunction "RESET_12") (pintype "bidirectional"))
      (node (ref "R16") (pin "1") (pinfunction "1_1") (pintype "passive"))
    )
    (net (code "124") (name "Net-(IC7-G)") (class "Default")
      (node (ref "IC7") (pin "3") (pinfunction "G_3") (pintype "passive"))
      (node (ref "R1") (pin "1") (pinfunction "1_1") (pintype "passive"))
      (node (ref "R2") (pin "1") (pinfunction "1_1") (pintype "passive"))
    )
    (net (code "125") (name "Net-(IC8-(INT1)PD3)") (class "Default")
      (node (ref "IC8") (pin "12") (pinfunction "(INT1)PD3_12") (pintype "bidirectional"))
      (node (ref "SJ1") (pin "1") (pinfunction "1_1") (pintype "passive"))
      (node (ref "SJ2") (pin "1") (pinfunction "1_1") (pintype "passive"))
    )
    (net (code "126") (name "Net-(IC8-AREF)") (class "Default")
      (node (ref "C7") (pin "1") (pinfunction "1_1") (pintype "passive"))
      (node (ref "IC8") (pin "29") (pinfunction "AREF_29") (pintype "passive"))
    )
    (net (code "127") (name "Net-(IC8-AVCC)") (class "Default")
      (node (ref "C6") (pin "1") (pinfunction "1_1") (pintype "passive"))
      (node (ref "IC8") (pin "27") (pinfunction "AVCC_27") (pintype "power_in"))
    )
    (net (code "128") (name "Net-(IC8-XTAL1)") (class "Default")
      (node (ref "C3") (pin "1") (pinfunction "1_1") (pintype "passive"))
      (node (ref "IC8") (pin "8") (pinfunction "XTAL1_8") (pintype "bidirectional"))
      (node (ref "Q2") (pin "1") (pinfunction "1_1") (pintype "passive"))
    )
    (net (code "129") (name "Net-(IC8-XTAL2)") (class "Default")
      (node (ref "C4") (pin "1") (pinfunction "1_1") (pintype "passive"))
      (node (ref "IC8") (pin "7") (pinfunction "XTAL2_7") (pintype "bidirectional"))
      (node (ref "Q2") (pin "2") (pinfunction "2_2") (pintype "passive"))
    )
    (net (code "130") (name "Net-(IC10A-O)") (class "Default")
      (node (ref "IC10") (pin "3") (pinfunction "O_3") (pintype "output"))
      (node (ref "IC10") (pin "5") (pinfunction "I0_5") (pintype "input"))
      (node (ref "IC10") (pin "6") (pinfunction "I1_6") (pintype "input"))
      (node (ref "SJ14") (pin "2") (pinfunction "2_2") (pintype "passive"))
    )
    (net (code "131") (name "Net-(IC10B-O)") (class "Default")
      (node (ref "IC10") (pin "4") (pinfunction "O_4") (pintype "output"))
      (node (ref "IC10") (pin "8") (pinfunction "I0_8") (pintype "input"))
      (node (ref "IC10") (pin "9") (pinfunction "I1_9") (pintype "input"))
      (node (ref "SJ15") (pin "2") (pinfunction "2_2") (pintype "passive"))
    )
    (net (code "132") (name "Net-(IC10C-O)") (class "Default")
      (node (ref "IC10") (pin "10") (pinfunction "O_10") (pintype "output"))
      (node (ref "IC10") (pin "12") (pinfunction "I0_12") (pintype "input"))
      (node (ref "IC10") (pin "13") (pinfunction "I1_13") (pintype "input"))
      (node (ref "R29") (pin "2") (pinfunction "2_2") (pintype "passive"))
      (node (ref "TP17") (pin "TP") (pinfunction "TP_TP") (pintype "bidirectional"))
    )
    (net (code "133") (name "Net-(IC10D-O)") (class "Default")
      (node (ref "IC10") (pin "11") (pinfunction "O_11") (pintype "output"))
      (node (ref "R30") (pin "2") (pinfunction "2_2") (pintype "passive"))
      (node (ref "TP7") (pin "TP") (pinfunction "TP_TP") (pintype "bidirectional"))
    )
    (net (code "134") (name "Net-(LED2-PadC)") (class "Default")
      (node (ref "LED2") (pin "C") (pinfunction "C_C") (pintype "passive"))
      (node (ref "R5") (pin "2") (pinfunction "2_2") (pintype "passive"))
    )
    (net (code "135") (name "Net-(LED7-PadC)") (class "Default")
      (node (ref "LED7") (pin "C") (pinfunction "C_C") (pintype "passive"))
      (node (ref "R18") (pin "2") (pinfunction "2_2") (pintype "passive"))
    )
    (net (code "136") (name "Net-(LED14-PadC)") (class "Default")
      (node (ref "LED14") (pin "C") (pinfunction "C_C") (pintype "passive"))
      (node (ref "R69") (pin "2") (pinfunction "2_2") (pintype "passive"))
    )
    (net (code "137") (name "Net-(LED15-PadC)") (class "Default")
      (node (ref "LED15") (pin "C") (pinfunction "C_C") (pintype "passive"))
      (node (ref "R70") (pin "2") (pinfunction "2_2") (pintype "passive"))
    )
    (net (code "138") (name "Net-(M1-+)") (class "Default")
      (node (ref "D9") (pin "C") (pinfunction "C_C") (pintype "passive"))
      (node (ref "M1") (pin "1") (pinfunction "+_1") (pintype "bidirectional"))
      (node (ref "R3") (pin "2") (pinfunction "2_2") (pintype "passive"))
    )
    (net (code "139") (name "Net-(M1--)") (class "Default")
      (node (ref "D9") (pin "A") (pinfunction "A_A") (pintype "passive"))
      (node (ref "IC7") (pin "1") (pinfunction "D_1") (pintype "passive"))
      (node (ref "IC7") (pin "2") (pinfunction "D_2") (pintype "bidirectional"))
      (node (ref "IC7") (pin "5") (pinfunction "D_5") (pintype "bidirectional"))
      (node (ref "IC7") (pin "6") (pinfunction "D_6") (pintype "bidirectional"))
      (node (ref "M1") (pin "2") (pinfunction "-_2") (pintype "bidirectional"))
    )
    (net (code "140") (name "Net-(R17-Pad1)") (class "Default")
      (node (ref "R17") (pin "1") (pinfunction "1_1") (pintype "passive"))
      (node (ref "SJ6") (pin "1") (pinfunction "1_1") (pintype "passive"))
    )
    (net (code "141") (name "Net-(R19-Pad1)") (class "Default")
      (node (ref "R19") (pin "1") (pinfunction "1_1") (pintype "passive"))
      (node (ref "SJ7") (pin "1") (pinfunction "1_1") (pintype "passive"))
    )
    (net (code "142") (name "Net-(R27-Pad1)") (class "Default")
      (node (ref "R27") (pin "1") (pinfunction "1_1") (pintype "passive"))
      (node (ref "SJ1") (pin "2") (pinfunction "2_2") (pintype "passive"))
    )
    (net (code "143") (name "Net-(R29-Pad1)") (class "Default")
      (node (ref "R29") (pin "1") (pinfunction "1_1") (pintype "passive"))
      (node (ref "SJ12") (pin "2") (pinfunction "2_2") (pintype "passive"))
    )
    (net (code "144") (name "Net-(R30-Pad1)") (class "Default")
      (node (ref "R30") (pin "1") (pinfunction "1_1") (pintype "passive"))
      (node (ref "SJ13") (pin "2") (pinfunction "2_2") (pintype "passive"))
    )
    (net (code "145") (name "Net-(R52-Pad2)") (class "Default")
      (node (ref "R52") (pin "2") (pinfunction "2_2") (pintype "passive"))
      (node (ref "SJ3") (pin "1") (pinfunction "1_1") (pintype "passive"))
    )
    (net (code "146") (name "Net-(R53-Pad2)") (class "Default")
      (node (ref "R53") (pin "2") (pinfunction "2_2") (pintype "passive"))
      (node (ref "SJ4") (pin "1") (pinfunction "1_1") (pintype "passive"))
    )
    (net (code "147") (name "Net-(R69-Pad1)") (class "Default")
      (node (ref "R69") (pin "1") (pinfunction "1_1") (pintype "passive"))
      (node (ref "SJ14") (pin "1") (pinfunction "1_1") (pintype "passive"))
    )
    (net (code "148") (name "Net-(R70-Pad1)") (class "Default")
      (node (ref "R70") (pin "1") (pinfunction "1_1") (pintype "passive"))
      (node (ref "SJ15") (pin "1") (pinfunction "1_1") (pintype "passive"))
    )
    (net (code "149") (name "Net-(R71-Pad2)") (class "Default")
      (node (ref "R71") (pin "2") (pinfunction "2_2") (pintype "passive"))
      (node (ref "SJ5") (pin "1") (pinfunction "1_1") (pintype "passive"))
    )
    (net (code "150") (name "Net-(XB3-D+)") (class "Default")
      (node (ref "POWER_CON_1") (pin "2") (pinfunction "2_2") (pintype "passive"))
      (node (ref "XB3") (pin "3") (pinfunction "D+_3") (pintype "bidirectional"))
    )
    (net (code "151") (name "Net-(XB3-D-)") (class "Default")
      (node (ref "POWER_CON_1") (pin "5") (pinfunction "5_5") (pintype "passive"))
      (node (ref "XB3") (pin "2") (pinfunction "D-_2") (pintype "bidirectional"))
    )
    (net (code "152") (name "Net-(XB3-GND)") (class "Default")
      (node (ref "POWER_CON_1") (pin "1") (pinfunction "1_1") (pintype "passive"))
      (node (ref "POWER_CON_1") (pin "3") (pinfunction "3_3") (pintype "passive"))
      (node (ref "XB3") (pin "10") (pinfunction "SHIELD_10") (pintype "bidirectional"))
      (node (ref "XB3") (pin "11") (pinfunction "SHIELD_11") (pintype "bidirectional"))
      (node (ref "XB3") (pin "5") (pinfunction "GND_5") (pintype "bidirectional"))
      (node (ref "XB3") (pin "6") (pinfunction "SHIELD_6") (pintype "bidirectional"))
      (node (ref "XB3") (pin "7") (pinfunction "SHIELD_7") (pintype "bidirectional"))
      (node (ref "XB3") (pin "8") (pinfunction "SHIELD_8") (pintype "bidirectional"))
      (node (ref "XB3") (pin "9") (pinfunction "SHIELD_9") (pintype "bidirectional"))
    )
    (net (code "153") (name "Net-(XB3-VBUS)") (class "Default")
      (node (ref "POWER_CON_1") (pin "4") (pinfunction "4_4") (pintype "passive"))
      (node (ref "POWER_CON_1") (pin "6") (pinfunction "6_6") (pintype "passive"))
      (node (ref "XB3") (pin "1") (pinfunction "VBUS_1") (pintype "bidirectional"))
    )
    (net (code "154") (name "PUSHBUTTON") (class "Default")
      (node (ref "C18") (pin "1") (pinfunction "1_1") (pintype "passive"))
      (node (ref "ENC1") (pin "D") (pinfunction "D_D") (pintype "bidirectional"))
      (node (ref "ENC2") (pin "6") (pinfunction "2_6") (pintype "bidirectional"))
      (node (ref "FFC2") (pin "11") (pinfunction "11_11") (pintype "passive"))
      (node (ref "R24") (pin "1") (pinfunction "1_1") (pintype "passive"))
    )
    (net (code "155") (name "PUSHBUTTON_TO_CONNECTOR") (class "Default")
      (node (ref "D6") (pin "C") (pinfunction "C_C") (pintype "passive"))
      (node (ref "FFC1") (pin "6") (pinfunction "6_6") (pintype "passive"))
      (node (ref "IC8") (pin "14") (pinfunction "(OC1A)PD5_14") (pintype "bidirectional"))
    )
    (net (code "156") (name "PWM_DOWN") (class "Default")
      (node (ref "C27") (pin "1") (pinfunction "1_1") (pintype "passive"))
      (node (ref "FFC2") (pin "7") (pinfunction "7_7") (pintype "passive"))
      (node (ref "R9") (pin "2") (pinfunction "2_2") (pintype "passive"))
      (node (ref "T2") (pin "1") (pinfunction "1_1") (pintype "bidirectional"))
      (node (ref "T2") (pin "2") (pinfunction "2_2") (pintype "bidirectional"))
    )
    (net (code "157") (name "PWM_DOWN_TO_CONNECTOR") (class "Default")
      (node (ref "D10") (pin "C") (pinfunction "C_C") (pintype "passive"))
      (node (ref "FFC1") (pin "10") (pinfunction "10_10") (pintype "passive"))
      (node (ref "IC8") (pin "22") (pinfunction "(TMS)PC3_22") (pintype "bidirectional"))
    )
    (net (code "158") (name "PWM_UP") (class "Default")
      (node (ref "C28") (pin "1") (pinfunction "1_1") (pintype "passive"))
      (node (ref "FFC2") (pin "9") (pinfunction "9_9") (pintype "passive"))
      (node (ref "R8") (pin "2") (pinfunction "2_2") (pintype "passive"))
      (node (ref "T1") (pin "1") (pinfunction "1_1") (pintype "bidirectional"))
      (node (ref "T1") (pin "2") (pinfunction "2_2") (pintype "bidirectional"))
    )
    (net (code "159") (name "PWM_UP_TO_CONNECTOR") (class "Default")
      (node (ref "D5") (pin "C") (pinfunction "C_C") (pintype "passive"))
      (node (ref "FFC1") (pin "8") (pinfunction "8_8") (pintype "passive"))
      (node (ref "IC8") (pin "21") (pinfunction "(TCK)PC2_21") (pintype "bidirectional"))
    )
    (net (code "160") (name "RESET_ATMEL") (class "Default")
      (node (ref "C5") (pin "1") (pinfunction "1_1") (pintype "passive"))
      (node (ref "IC8") (pin "4") (pinfunction "RESET_4") (pintype "input"))
      (node (ref "R7") (pin "1") (pinfunction "1_1") (pintype "passive"))
      (node (ref "XW1") (pin "5") (pinfunction "RESET_5") (pintype "bidirectional"))
    )
    (net (code "161") (name "RTC8564_INT") (class "Default")
      (node (ref "IC2") (pin "10") (pinfunction "INT\\_10") (pintype "output"))
      (node (ref "IC8") (pin "11") (pinfunction "(INT0)PD2_11") (pintype "bidirectional"))
      (node (ref "R20") (pin "1") (pinfunction "1_1") (pintype "passive"))
    )
    (net (code "162") (name "SCK") (class "Default")
      (node (ref "IC8") (pin "3") (pinfunction "(SCK)PB7_3") (pintype "bidirectional"))
      (node (ref "XW1") (pin "3") (pinfunction "SCK_3") (pintype "bidirectional"))
    )
    (net (code "163") (name "SCL") (class "Default")
      (node (ref "CON_TOUCH_SENSOR_2") (pin "3") (pinfunction "3_3") (pintype "passive"))
      (node (ref "IC2") (pin "6") (pinfunction "SCL_6") (pintype "input"))
      (node (ref "IC8") (pin "19") (pinfunction "PC0(SCL)_19") (pintype "bidirectional"))
      (node (ref "IC9") (pin "3") (pinfunction "SCL_3") (pintype "bidirectional"))
      (node (ref "R52") (pin "1") (pinfunction "1_1") (pintype "passive"))
      (node (ref "TP6") (pin "TP") (pinfunction "TP_TP") (pintype "bidirectional"))
    )
    (net (code "164") (name "SCL_TOUCH_SENSOR") (class "Default")
      (node (ref "CON_TOUCH_SENSOR_1") (pin "4") (pinfunction "4_4") (pintype "passive"))
      (node (ref "IC6") (pin "14") (pinfunction "SCL_14") (pintype "bidirectional"))
      (node (ref "R17") (pin "2") (pinfunction "2_2") (pintype "passive"))
      (node (ref "TP12") (pin "TP") (pinfunction "TP_TP") (pintype "bidirectional"))
    )
    (net (code "165") (name "SDA") (class "Default")
      (node (ref "CON_TOUCH_SENSOR_2") (pin "4") (pinfunction "4_4") (pintype "passive"))
      (node (ref "IC2") (pin "7") (pinfunction "SDA_7") (pintype "bidirectional"))
      (node (ref "IC8") (pin "20") (pinfunction "PC1(SDA)_20") (pintype "bidirectional"))
      (node (ref "IC9") (pin "4") (pinfunction "SDA_4") (pintype "bidirectional"))
      (node (ref "R53") (pin "1") (pinfunction "1_1") (pintype "passive"))
      (node (ref "TP5") (pin "TP") (pinfunction "TP_TP") (pintype "bidirectional"))
    )
    (net (code "166") (name "SDA_TOUCH_SENSOR") (class "Default")
      (node (ref "CON_TOUCH_SENSOR_1") (pin "3") (pinfunction "3_3") (pintype "passive"))
      (node (ref "IC6") (pin "11") (pinfunction "SDA_11") (pintype "bidirectional"))
      (node (ref "R19") (pin "2") (pinfunction "2_2") (pintype "passive"))
      (node (ref "TP13") (pin "TP") (pinfunction "TP_TP") (pintype "bidirectional"))
    )
    (net (code "167") (name "SET+") (class "Default")
      (node (ref "C12") (pin "1") (pinfunction "1_1") (pintype "passive"))
      (node (ref "FFC2") (pin "5") (pinfunction "5_5") (pintype "passive"))
      (node (ref "R64") (pin "2") (pinfunction "2_2") (pintype "passive"))
      (node (ref "T3") (pin "1") (pinfunction "1_1") (pintype "bidirectional"))
      (node (ref "T3") (pin "2") (pinfunction "2_2") (pintype "bidirectional"))
    )
    (net (code "168") (name "SET+_TO_CONNECTOR") (class "Default")
      (node (ref "D4") (pin "C") (pinfunction "C_C") (pintype "passive"))
      (node (ref "FFC1") (pin "12") (pinfunction "12_12") (pintype "passive"))
      (node (ref "IC8") (pin "23") (pinfunction "(TDO)PC4_23") (pintype "bidirectional"))
    )
    (net (code "169") (name "SET-") (class "Default")
      (node (ref "C10") (pin "1") (pinfunction "1_1") (pintype "passive"))
      (node (ref "FFC2") (pin "3") (pinfunction "3_3") (pintype "passive"))
      (node (ref "R72") (pin "2") (pinfunction "2_2") (pintype "passive"))
      (node (ref "T4") (pin "1") (pinfunction "1_1") (pintype "bidirectional"))
      (node (ref "T4") (pin "2") (pinfunction "2_2") (pintype "bidirectional"))
    )
    (net (code "170") (name "SET-_TO_CONNECTOR") (class "Default")
      (node (ref "D3") (pin "C") (pinfunction "C_C") (pintype "passive"))
      (node (ref "FFC1") (pin "14") (pinfunction "14_14") (pintype "passive"))
      (node (ref "IC8") (pin "24") (pinfunction "(TDI)PC5_24") (pintype "bidirectional"))
    )
    (net (code "171") (name "SOUND") (class "Default")
      (node (ref "IC8") (pin "44") (pinfunction "(SS)PB4_44") (pintype "bidirectional"))
      (node (ref "R10") (pin "2") (pinfunction "2_2") (pintype "passive"))
    )
    (net (code "172") (name "SUPPLY_3V3_DCF77") (class "Default")
      (node (ref "A3") (pin "3") (pinfunction "VCC_3") (pintype "bidirectional"))
      (node (ref "C11") (pin "1") (pinfunction "1_1") (pintype "passive"))
      (node (ref "C25") (pin "1") (pinfunction "1_1") (pintype "passive"))
      (node (ref "CON_DCF_1") (pin "5") (pinfunction "5_5") (pintype "passive"))
      (node (ref "CON_DCF_1") (pin "6") (pinfunction "6_6") (pintype "passive"))
      (node (ref "IC10") (pin "14") (pinfunction "VDD_14") (pintype "power_in"))
      (node (ref "LED14") (pin "A") (pinfunction "A_A") (pintype "passive"))
      (node (ref "LED15") (pin "A") (pinfunction "A_A") (pintype "passive"))
      (node (ref "R71") (pin "1") (pinfunction "1_1") (pintype "passive"))
      (node (ref "TP18") (pin "TP") (pinfunction "TP_TP") (pintype "bidirectional"))
    )
    (net (code "173") (name "SUPPLY_RTC") (class "Default")
      (node (ref "C1") (pin "1") (pinfunction "1_1") (pintype "passive"))
      (node (ref "C30") (pin "+") (pinfunction "+_+") (pintype "passive"))
      (node (ref "C31") (pin "PLUS") (pinfunction "+_PLUS") (pintype "passive"))
      (node (ref "D1") (pin "C") (pinfunction "C_C") (pintype "passive"))
      (node (ref "IC2") (pin "4") (pinfunction "VDD_4") (pintype "power_in"))
      (node (ref "R4") (pin "2") (pinfunction "2_2") (pintype "passive"))
    )
    (net (code "174") (name "VCC") (class "Default")
      (node (ref "C17") (pin "1") (pinfunction "1_1") (pintype "passive"))
      (node (ref "C20") (pin "1") (pinfunction "1_1") (pintype "passive"))
      (node (ref "C22") (pin "+") (pinfunction "+_+") (pintype "passive"))
      (node (ref "C29") (pin "+") (pinfunction "+_+") (pintype "passive"))
      (node (ref "D7") (pin "C") (pinfunction "C_C") (pintype "passive"))
      (node (ref "IC1") (pin "7") (pinfunction "REGIN_7") (pintype "bidirectional"))
      (node (ref "IC1") (pin "8") (pinfunction "VBUS_8") (pintype "bidirectional"))
      (node (ref "IC11") (pin "1") (pinfunction "VCC_1") (pintype "bidirectional"))
      (node (ref "IC4") (pin "6") (pinfunction "VIN_6") (pintype "bidirectional"))
      (node (ref "R21") (pin "1") (pinfunction "1_1") (pintype "passive"))
      (node (ref "TP10") (pin "TP") (pinfunction "TP_TP") (pintype "bidirectional"))
    )
    (net (code "175") (name "VIBRO_MOTOR") (class "Default")
      (node (ref "IC8") (pin "43") (pinfunction "(AIN1/OC0)PB3_43") (pintype "bidirectional"))
      (node (ref "R1") (pin "2") (pinfunction "2_2") (pintype "passive"))
    )
    (net (code "176") (name "unconnected-(IC1-CTS-Pad23)") (class "Default")
      (node (ref "IC1") (pin "23") (pinfunction "CTS_23") (pintype "bidirectional"))
    )
    (net (code "177") (name "unconnected-(IC1-DCD-Pad1)") (class "Default")
      (node (ref "IC1") (pin "1") (pinfunction "DCD_1") (pintype "bidirectional"))
    )
    (net (code "178") (name "unconnected-(IC1-DSR-Pad27)") (class "Default")
      (node (ref "IC1") (pin "27") (pinfunction "DSR_27") (pintype "bidirectional"))
    )
    (net (code "179") (name "unconnected-(IC1-DTR-Pad28)") (class "Default")
      (node (ref "IC1") (pin "28") (pinfunction "DTR_28") (pintype "bidirectional"))
    )
    (net (code "180") (name "unconnected-(IC1-RI-Pad2)") (class "Default")
      (node (ref "IC1") (pin "2") (pinfunction "RI_2") (pintype "bidirectional"))
    )
    (net (code "181") (name "unconnected-(IC1-RTS-Pad24)") (class "Default")
      (node (ref "IC1") (pin "24") (pinfunction "RTS_24") (pintype "bidirectional"))
    )
    (net (code "182") (name "unconnected-(IC1-SUSPEND_HIGH-Pad12)") (class "Default")
      (node (ref "IC1") (pin "12") (pinfunction "SUSPEND_HIGH_12") (pintype "bidirectional"))
    )
    (net (code "183") (name "unconnected-(IC1-SUSPEND_LOW-Pad11)") (class "Default")
      (node (ref "IC1") (pin "11") (pinfunction "SUSPEND_LOW_11") (pintype "bidirectional"))
    )
    (net (code "184") (name "unconnected-(IC2-NC-Pad1)") (class "Default")
      (node (ref "IC2") (pin "1") (pinfunction "NC_1") (pintype "no_connect"))
    )
    (net (code "185") (name "unconnected-(IC2-NC-Pad2)") (class "Default")
      (node (ref "IC2") (pin "2") (pinfunction "NC_2") (pintype "no_connect"))
    )
    (net (code "186") (name "unconnected-(IC2-NC-Pad11)") (class "Default")
      (node (ref "IC2") (pin "11") (pinfunction "NC_11") (pintype "no_connect"))
    )
    (net (code "187") (name "unconnected-(IC2-NC-Pad12)") (class "Default")
      (node (ref "IC2") (pin "12") (pinfunction "NC_12") (pintype "no_connect"))
    )
    (net (code "188") (name "unconnected-(IC2-NC-Pad13)") (class "Default")
      (node (ref "IC2") (pin "13") (pinfunction "NC_13") (pintype "no_connect"))
    )
    (net (code "189") (name "unconnected-(IC2-NC-Pad14)") (class "Default")
      (node (ref "IC2") (pin "14") (pinfunction "NC_14") (pintype "no_connect"))
    )
    (net (code "190") (name "unconnected-(IC2-NC-Pad15)") (class "Default")
      (node (ref "IC2") (pin "15") (pinfunction "NC_15") (pintype "no_connect"))
    )
    (net (code "191") (name "unconnected-(IC2-NC-Pad16)") (class "Default")
      (node (ref "IC2") (pin "16") (pinfunction "NC_16") (pintype "no_connect"))
    )
    (net (code "192") (name "unconnected-(IC2-NC-Pad17)") (class "Default")
      (node (ref "IC2") (pin "17") (pinfunction "NC_17") (pintype "no_connect"))
    )
    (net (code "193") (name "unconnected-(IC2-NC-Pad18)") (class "Default")
      (node (ref "IC2") (pin "18") (pinfunction "NC_18") (pintype "no_connect"))
    )
    (net (code "194") (name "unconnected-(IC2-NC-Pad19)") (class "Default")
      (node (ref "IC2") (pin "19") (pinfunction "NC_19") (pintype "no_connect"))
    )
    (net (code "195") (name "unconnected-(IC2-NC-Pad20)") (class "Default")
      (node (ref "IC2") (pin "20") (pinfunction "NC_20") (pintype "no_connect"))
    )
    (net (code "196") (name "unconnected-(IC6-KEY6-Pad1)") (class "Default")
      (node (ref "IC6") (pin "1") (pinfunction "KEY6_1") (pintype "bidirectional"))
    )
    (net (code "197") (name "unconnected-(IC6-KEY7-Pad20)") (class "Default")
      (node (ref "IC6") (pin "20") (pinfunction "KEY7_20") (pintype "bidirectional"))
    )
    (net (code "198") (name "unconnected-(IC6-KEY8-Pad19)") (class "Default")
      (node (ref "IC6") (pin "19") (pinfunction "KEY8_19") (pintype "bidirectional"))
    )
    (net (code "199") (name "unconnected-(IC6-KEY9-Pad18)") (class "Default")
      (node (ref "IC6") (pin "18") (pinfunction "KEY9_18") (pintype "bidirectional"))
    )
    (net (code "200") (name "unconnected-(IC6-KEY10-Pad17)") (class "Default")
      (node (ref "IC6") (pin "17") (pinfunction "KEY10_17") (pintype "bidirectional"))
    )
    (net (code "201") (name "unconnected-(IC6-KEY11-Pad16)") (class "Default")
      (node (ref "IC6") (pin "16") (pinfunction "KEY11_16") (pintype "bidirectional"))
    )
    (net (code "202") (name "unconnected-(IC6-NC-Pad13)") (class "Default")
      (node (ref "IC6") (pin "13") (pinfunction "NC_13") (pintype "bidirectional"))
    )
    (net (code "203") (name "unconnected-(IC8-(ADC7)PA7-Pad30)") (class "Default")
      (node (ref "IC8") (pin "30") (pinfunction "(ADC7)PA7_30") (pintype "bidirectional"))
    )
    (net (code "204") (name "unconnected-(IC8-(T0{slash}XCK)PB0-Pad40)") (class "Default")
      (node (ref "IC8") (pin "40") (pinfunction "(T0/XCK)PB0_40") (pintype "bidirectional"))
    )
    (net (code "205") (name "unconnected-(IC8-(T1)PB1-Pad41)") (class "Default")
      (node (ref "IC8") (pin "41") (pinfunction "(T1)PB1_41") (pintype "bidirectional"))
    )
    (net (code "206") (name "unconnected-(IC8-(TOSC2)PC7-Pad26)") (class "Default")
      (node (ref "IC8") (pin "26") (pinfunction "(TOSC2)PC7_26") (pintype "bidirectional"))
    )
    (net (code "207") (name "unconnected-(IC11-NC-Pad2)") (class "Default")
      (node (ref "IC11") (pin "2") (pinfunction "NC_2") (pintype "bidirectional"))
    )
    (net (code "208") (name "unconnected-(IC11-NC-Pad5)") (class "Default")
      (node (ref "IC11") (pin "5") (pinfunction "NC_5") (pintype "bidirectional"))
    )
    (net (code "209") (name "unconnected-(XB3-ID-Pad4)") (class "Default")
      (node (ref "XB3") (pin "4") (pinfunction "ID_4") (pintype "bidirectional"))
    )
  )
)
